# motor_board_tmc.net
KiCad netlist of a schematic drawn in EAGLE
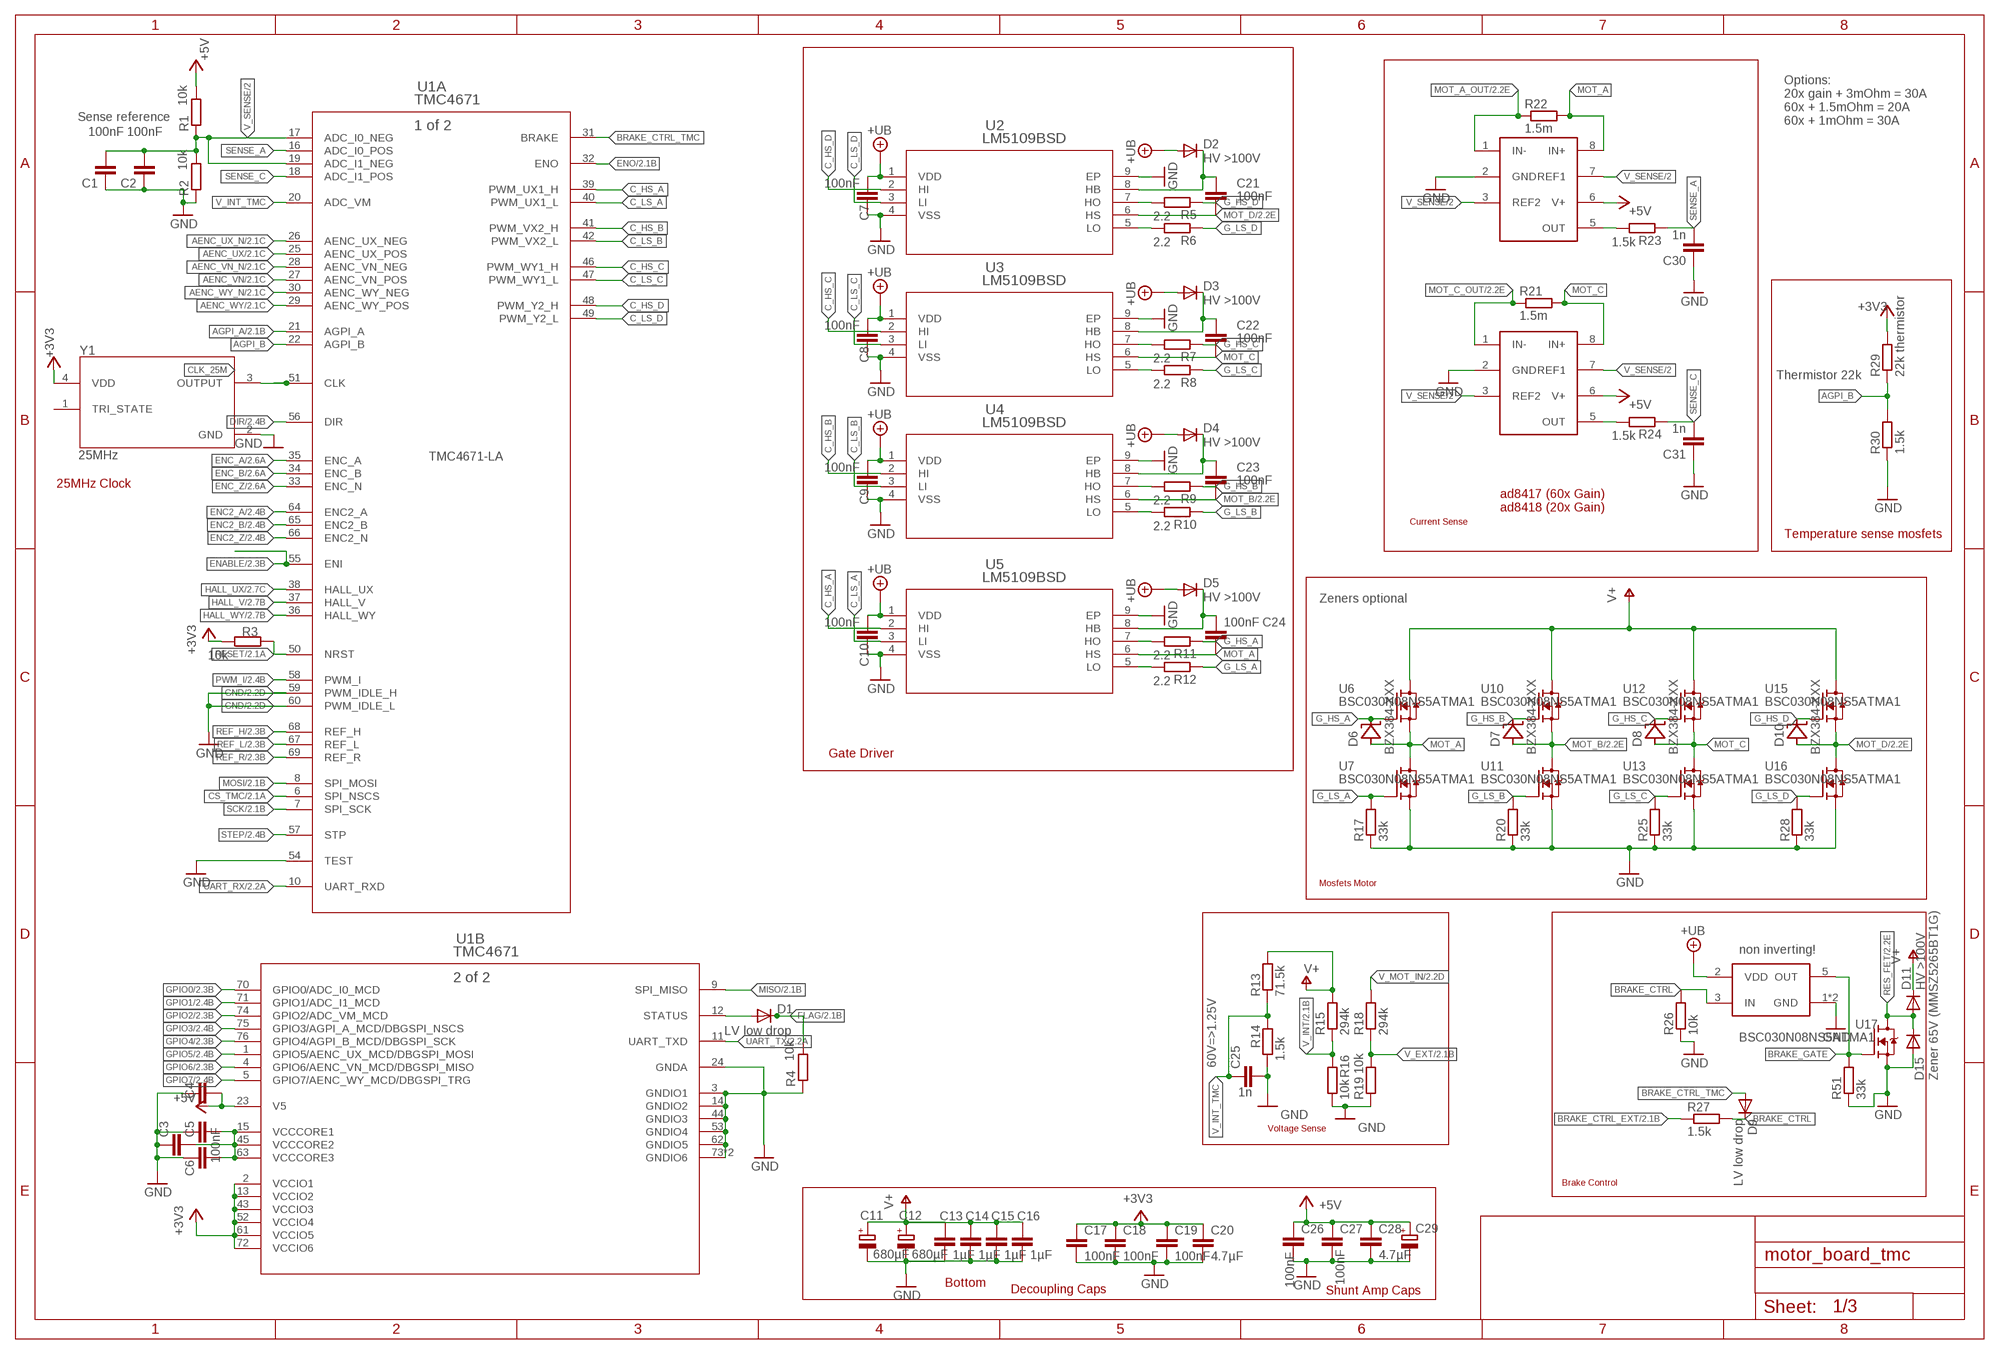
[diagram p0: schematic, sheet 1]
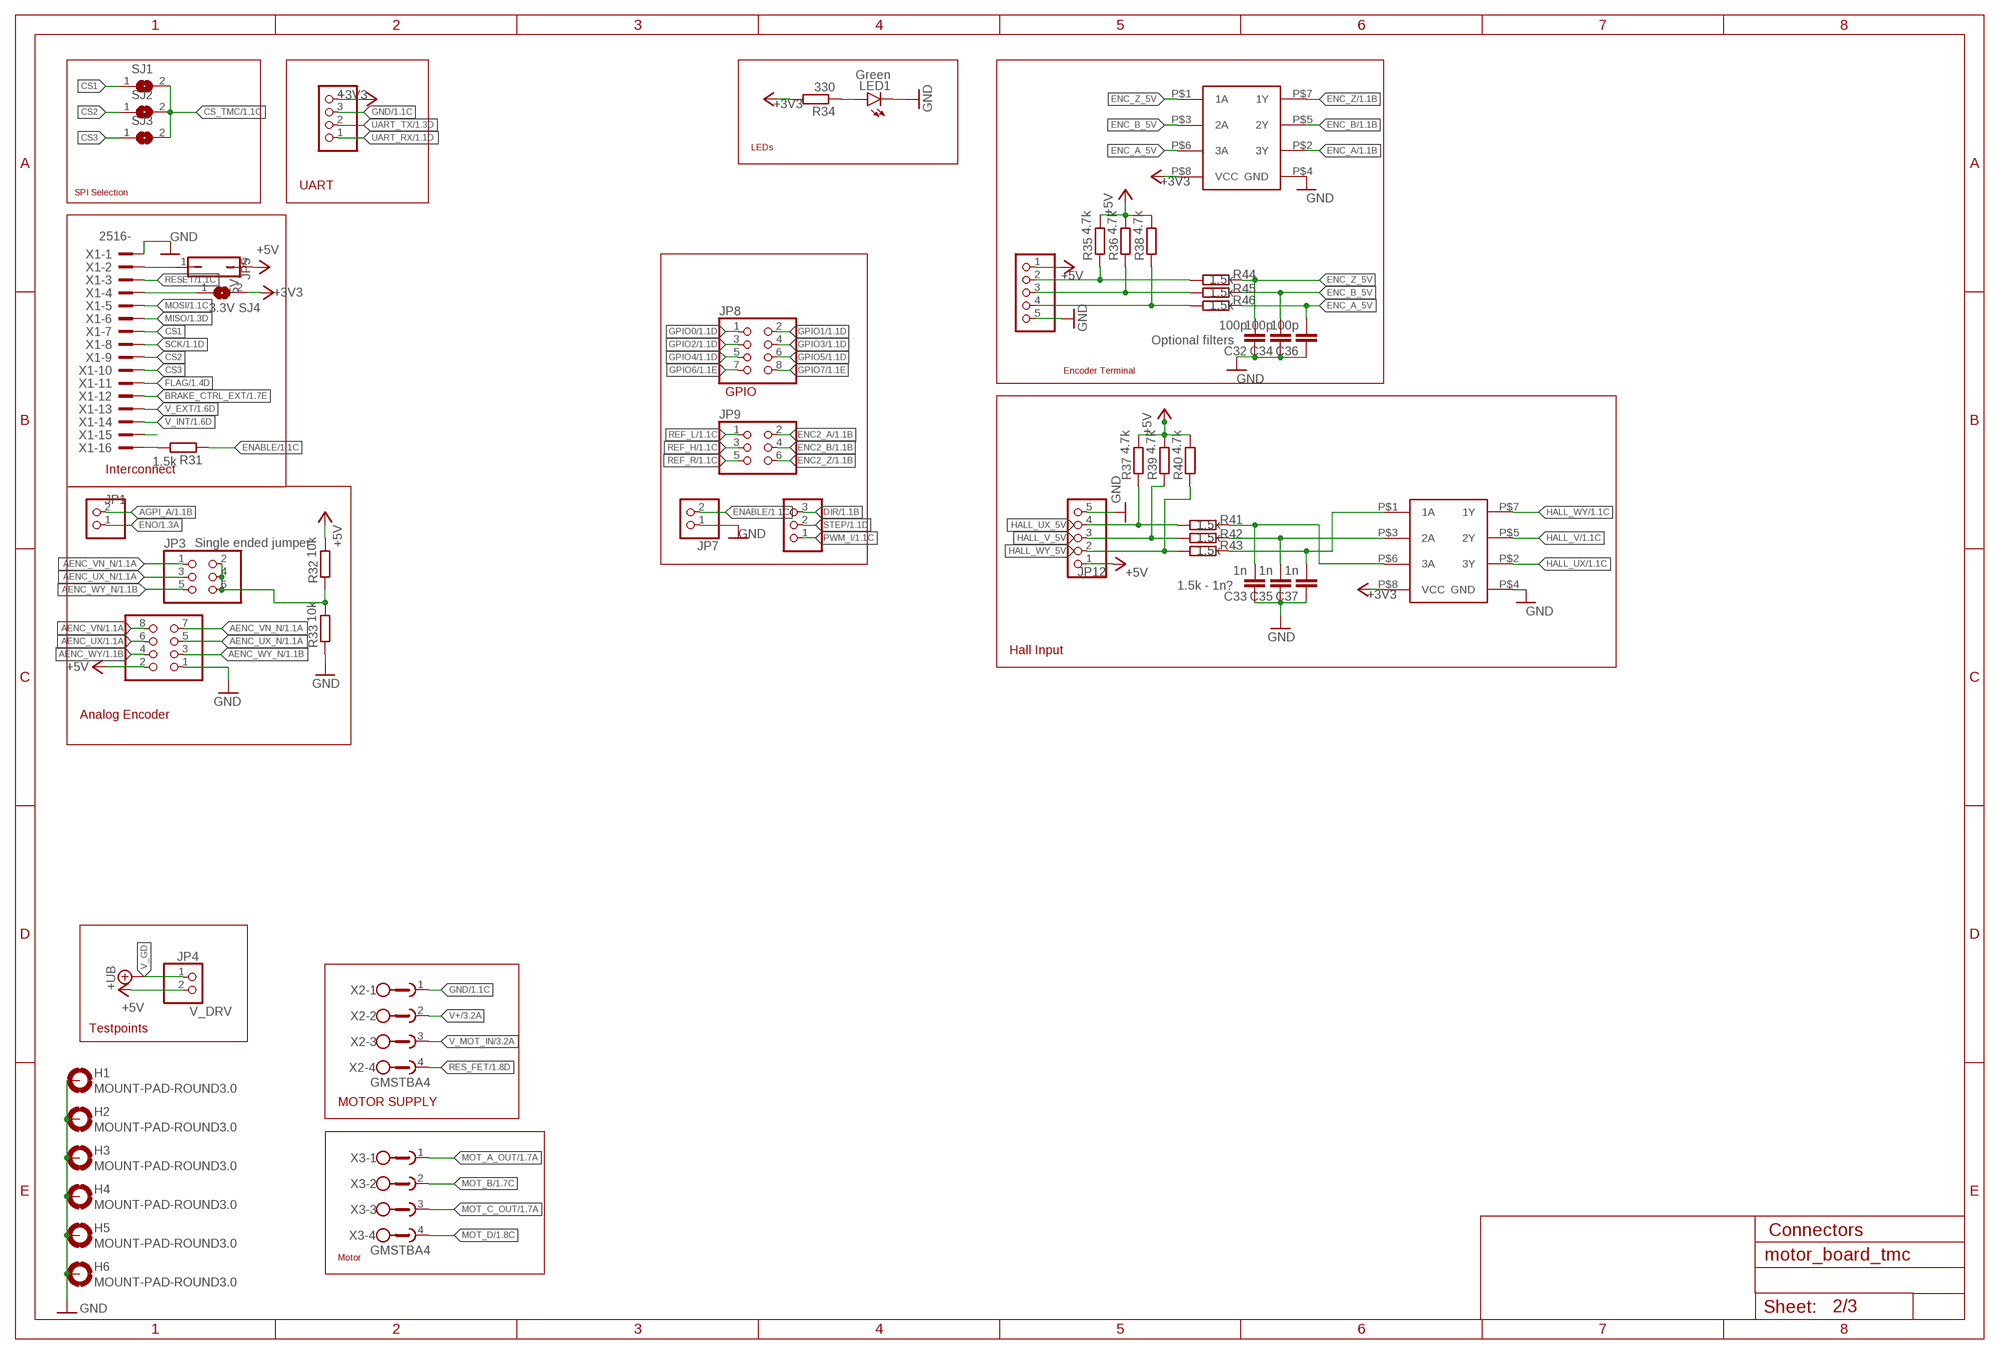
[diagram p1: schematic, sheet 2]
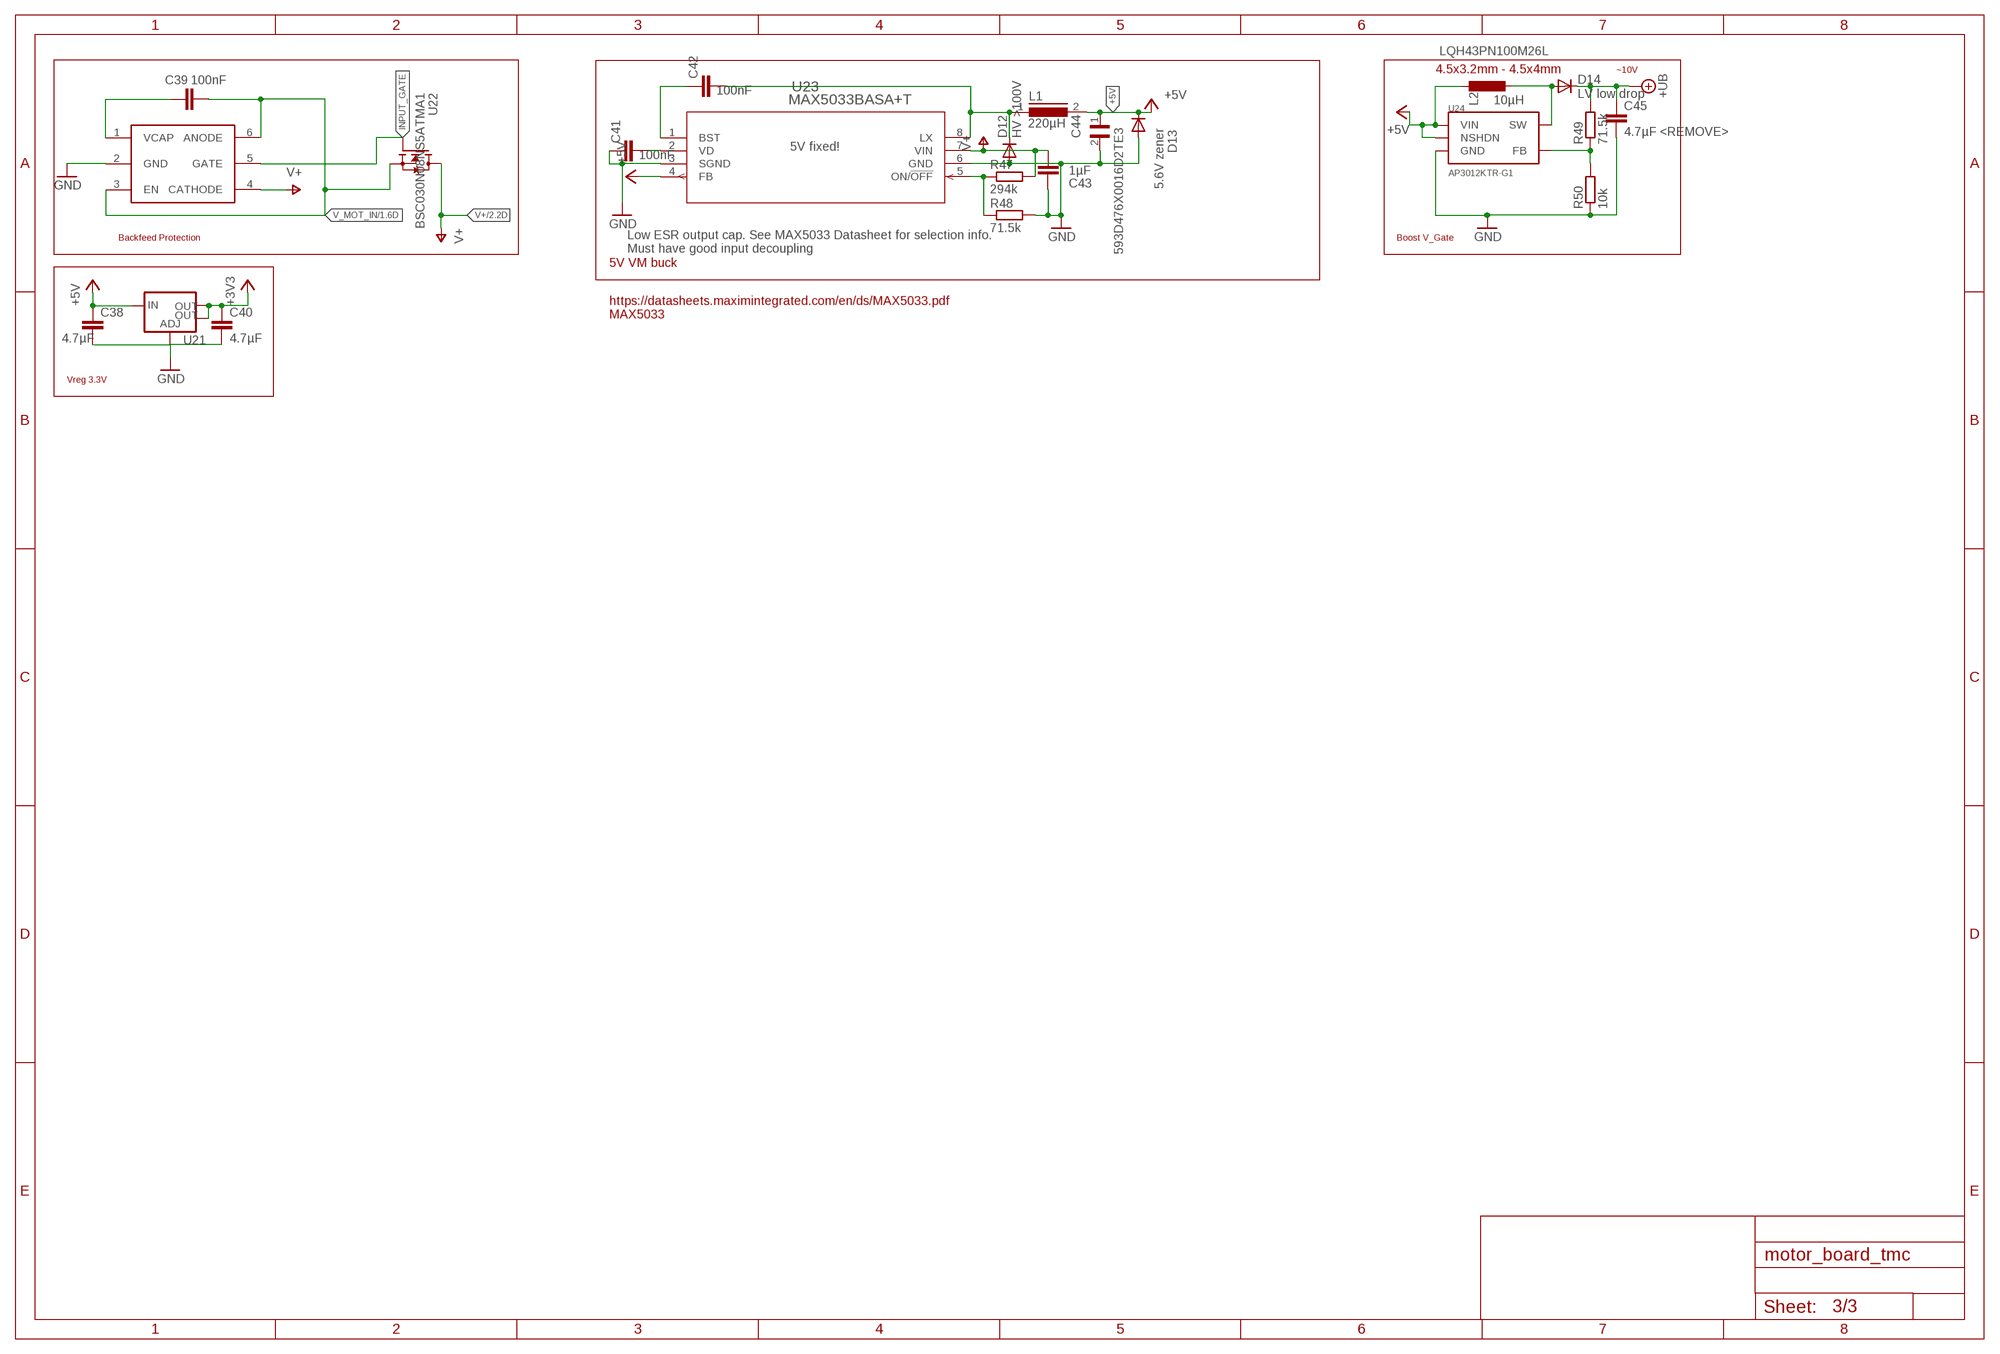
[diagram p2: schematic, sheet 3]

(export (version "E")
  (design (tool "Eeschema 10.0.6"))
  (components
    (comp (ref "C32")
      (value "100p")
      (footprint "eagle-import:C0603")
      (libsource (lib "eagle-import") (part "C-EUC0603"))
    )
    (comp (ref "C33")
      (value "1n")
      (footprint "eagle-import:C0603")
      (libsource (lib "eagle-import") (part "C-EUC0603"))
    )
    (comp (ref "C34")
      (value "100p")
      (footprint "eagle-import:C0603")
      (libsource (lib "eagle-import") (part "C-EUC0603"))
    )
    (comp (ref "C35")
      (value "1n")
      (footprint "eagle-import:C0603")
      (libsource (lib "eagle-import") (part "C-EUC0603"))
    )
    (comp (ref "C36")
      (value "100p")
      (footprint "eagle-import:C0603")
      (libsource (lib "eagle-import") (part "C-EUC0603"))
    )
    (comp (ref "C37")
      (value "1n")
      (footprint "eagle-import:C0603")
      (libsource (lib "eagle-import") (part "C-EUC0603"))
    )
    (comp (ref "H1")
      (value "MOUNT-PAD-ROUND3.0")
      (footprint "eagle-import:3,0-PAD")
      (libsource (lib "eagle-import") (part "MOUNT-PAD-ROUND3.0"))
    )
    (comp (ref "H2")
      (value "MOUNT-PAD-ROUND3.0")
      (footprint "eagle-import:3,0-PAD")
      (libsource (lib "eagle-import") (part "MOUNT-PAD-ROUND3.0"))
    )
    (comp (ref "H3")
      (value "MOUNT-PAD-ROUND3.0")
      (footprint "eagle-import:3,0-PAD")
      (libsource (lib "eagle-import") (part "MOUNT-PAD-ROUND3.0"))
    )
    (comp (ref "H4")
      (value "MOUNT-PAD-ROUND3.0")
      (footprint "eagle-import:3,0-PAD")
      (libsource (lib "eagle-import") (part "MOUNT-PAD-ROUND3.0"))
    )
    (comp (ref "H5")
      (value "MOUNT-PAD-ROUND3.0")
      (footprint "eagle-import:3,0-PAD")
      (libsource (lib "eagle-import") (part "MOUNT-PAD-ROUND3.0"))
    )
    (comp (ref "H6")
      (value "MOUNT-PAD-ROUND3.0")
      (footprint "eagle-import:3,0-PAD")
      (libsource (lib "eagle-import") (part "MOUNT-PAD-ROUND3.0"))
    )
    (comp (ref "JP1")
      (value "PINHD-1X2")
      (footprint "eagle-import:1X02")
      (libsource (lib "eagle-import") (part "PINHD-1X2"))
    )
    (comp (ref "JP2")
      (value "PINHD-2X4")
      (footprint "eagle-import:2X04")
      (libsource (lib "eagle-import") (part "PINHD-2X4"))
    )
    (comp (ref "JP3")
      (value "PINHD-2X3")
      (footprint "eagle-import:2X03")
      (libsource (lib "eagle-import") (part "PINHD-2X3"))
    )
    (comp (ref "JP4")
      (value "V_DRV")
      (footprint "eagle-import:1X02")
      (libsource (lib "eagle-import") (part "PINHD-1X2"))
    )
    (comp (ref "JP5")
      (value "5V")
      (footprint "eagle-import:JP1")
      (libsource (lib "eagle-import") (part "JP1Q"))
    )
    (comp (ref "JP6")
      (value "PINHD-1X4")
      (footprint "eagle-import:1X04")
      (libsource (lib "eagle-import") (part "PINHD-1X4"))
    )
    (comp (ref "JP7")
      (value "PINHD-1X2")
      (footprint "eagle-import:1X02")
      (libsource (lib "eagle-import") (part "PINHD-1X2"))
    )
    (comp (ref "JP8")
      (value "PINHD-2X4")
      (footprint "eagle-import:2X04")
      (libsource (lib "eagle-import") (part "PINHD-2X4"))
    )
    (comp (ref "JP9")
      (value "PINHD-2X3")
      (footprint "eagle-import:2X03")
      (libsource (lib "eagle-import") (part "PINHD-2X3"))
    )
    (comp (ref "JP10")
      (value "PINHD-1X3")
      (footprint "eagle-import:1X03")
      (libsource (lib "eagle-import") (part "PINHD-1X3"))
    )
    (comp (ref "JP11")
      (value "PINHD-1X5")
      (footprint "eagle-import:1X05")
      (libsource (lib "eagle-import") (part "PINHD-1X5"))
    )
    (comp (ref "JP12")
      (value "PINHD-1X5")
      (footprint "eagle-import:1X05")
      (libsource (lib "eagle-import") (part "PINHD-1X5"))
    )
    (comp (ref "LED1")
      (value "Green")
      (footprint "eagle-import:SML0805")
      (libsource (lib "eagle-import") (part "LEDSML0805"))
    )
    (comp (ref "R31")
      (value "1.5k")
      (footprint "eagle-import:R0603")
      (libsource (lib "eagle-import") (part "R-EU_R0603"))
    )
    (comp (ref "R32")
      (value "10k")
      (footprint "eagle-import:R0603")
      (libsource (lib "eagle-import") (part "R-EU_R0603"))
    )
    (comp (ref "R33")
      (value "10k")
      (footprint "eagle-import:R0603")
      (libsource (lib "eagle-import") (part "R-EU_R0603"))
    )
    (comp (ref "R34")
      (value "330")
      (footprint "eagle-import:R0603")
      (libsource (lib "eagle-import") (part "R-EU_R0603"))
    )
    (comp (ref "R35")
      (value "4.7k")
      (footprint "eagle-import:R0603")
      (libsource (lib "eagle-import") (part "R-EU_R0603"))
    )
    (comp (ref "R36")
      (value "4.7k")
      (footprint "eagle-import:R0603")
      (libsource (lib "eagle-import") (part "R-EU_R0603"))
    )
    (comp (ref "R37")
      (value "4.7k")
      (footprint "eagle-import:R0603")
      (libsource (lib "eagle-import") (part "R-EU_R0603"))
    )
    (comp (ref "R38")
      (value "4.7k")
      (footprint "eagle-import:R0603")
      (libsource (lib "eagle-import") (part "R-EU_R0603"))
    )
    (comp (ref "R39")
      (value "4.7k")
      (footprint "eagle-import:R0603")
      (libsource (lib "eagle-import") (part "R-EU_R0603"))
    )
    (comp (ref "R40")
      (value "4.7k")
      (footprint "eagle-import:R0603")
      (libsource (lib "eagle-import") (part "R-EU_R0603"))
    )
    (comp (ref "R41")
      (value "1.5k")
      (footprint "eagle-import:R0603")
      (libsource (lib "eagle-import") (part "R-EU_R0603"))
    )
    (comp (ref "R42")
      (value "1.5k")
      (footprint "eagle-import:R0603")
      (libsource (lib "eagle-import") (part "R-EU_R0603"))
    )
    (comp (ref "R43")
      (value "1.5k")
      (footprint "eagle-import:R0603")
      (libsource (lib "eagle-import") (part "R-EU_R0603"))
    )
    (comp (ref "R44")
      (value "1.5k")
      (footprint "eagle-import:R0603")
      (libsource (lib "eagle-import") (part "R-EU_R0603"))
    )
    (comp (ref "R45")
      (value "1.5k")
      (footprint "eagle-import:R0603")
      (libsource (lib "eagle-import") (part "R-EU_R0603"))
    )
    (comp (ref "R46")
      (value "1.5k")
      (footprint "eagle-import:R0603")
      (libsource (lib "eagle-import") (part "R-EU_R0603"))
    )
    (comp (ref "SJ1") (value "SJ") (footprint "eagle-import:SJ") (libsource (lib "eagle-import") (part "SJ")))
    (comp (ref "SJ2") (value "SJ") (footprint "eagle-import:SJ") (libsource (lib "eagle-import") (part "SJ")))
    (comp (ref "SJ3") (value "SJ") (footprint "eagle-import:SJ") (libsource (lib "eagle-import") (part "SJ")))
    (comp (ref "SJ4")
      (value "3.3V")
      (footprint "eagle-import:SJ")
      (libsource (lib "eagle-import") (part "SJ"))
    )
    (comp (ref "U18")
      (value "NC7NZ17K8X-3-BUFFER")
      (footprint "eagle-import:VFSOP-8")
      (libsource (lib "eagle-import") (part "NC7NZ17K8X-3-BUFFER"))
    )
    (comp (ref "U19")
      (value "NC7NZ17K8X-3-BUFFER")
      (footprint "eagle-import:VFSOP-8")
      (libsource (lib "eagle-import") (part "NC7NZ17K8X-3-BUFFER"))
    )
    (comp (ref "X1")
      (value "2516-")
      (footprint "eagle-import:PAK100_2500-16")
      (libsource (lib "eagle-import") (part "2516-"))
    )
    (comp (ref "X2")
      (value "GMSTBA4")
      (footprint "eagle-import:GMSTBA4")
      (fields (field (name "MF") "FARNELL") (field (name "MPN") "1757268"))
      (libsource (lib "eagle-import") (part "GMSTBA4"))
    )
    (comp (ref "X3")
      (value "GMSTBA4")
      (footprint "eagle-import:GMSTBA4")
      (fields (field (name "MF") "FARNELL") (field (name "MPN") "1757268"))
      (libsource (lib "eagle-import") (part "GMSTBA4"))
    )
    (comp (ref "C38")
      (value "4.7µF")
      (footprint "eagle-import:C0805")
      (libsource (lib "eagle-import") (part "C-EUC0805"))
    )
    (comp (ref "C39")
      (value "100nF")
      (footprint "eagle-import:C0805")
      (libsource (lib "eagle-import") (part "C-EUC0805"))
    )
    (comp (ref "C40")
      (value "4.7µF")
      (footprint "eagle-import:C0805")
      (libsource (lib "eagle-import") (part "C-EUC0805"))
    )
    (comp (ref "C41")
      (value "100nF")
      (footprint "eagle-import:C0603")
      (libsource (lib "eagle-import") (part "C-EUC0603"))
    )
    (comp (ref "C42")
      (value "100nF")
      (footprint "eagle-import:C0603")
      (libsource (lib "eagle-import") (part "C-EUC0603"))
    )
    (comp (ref "C43")
      (value "1µF")
      (footprint "eagle-import:C1206")
      (libsource (lib "eagle-import") (part "C-EUC1206"))
    )
    (comp (ref "C44")
      (value "593D476X0016D2TE3")
      (footprint "eagle-import:CAPPM7343X310N")
      (fields (field (name "DIGI-KEY_PART_NUMBER") "718-2142-1-ND") (field (name "MF") "Vishay Sprague"))
      (libsource (lib "eagle-import") (part "593D476X0016D2TE3"))
    )
    (comp (ref "C45")
      (value "4.7µF <REMOVE>")
      (footprint "eagle-import:C0805")
      (libsource (lib "eagle-import") (part "C-EUC0805"))
    )
    (comp (ref "D12")
      (value "HV >100V")
      (footprint "eagle-import:SOD-123FL")
      (libsource (lib "eagle-import") (part "DIODE_SOD-123FL"))
    )
    (comp (ref "D13")
      (value "5.6V zener")
      (footprint "eagle-import:SOD-123FL")
      (libsource (lib "eagle-import") (part "DIODE_SOD-123FL"))
    )
    (comp (ref "D14")
      (value "LV low drop")
      (footprint "eagle-import:SOD-123FL")
      (libsource (lib "eagle-import") (part "DIODE_SOD-123FL"))
    )
    (comp (ref "L1")
      (value "220µH")
      (footprint "eagle-import:8MMINDUCTOR")
      (libsource (lib "eagle-import") (part "8MMINDUCTOR"))
    )
    (comp (ref "L2")
      (value "10µH")
      (footprint "eagle-import:L4532P")
      (libsource (lib "eagle-import") (part "L-EUL4532P"))
    )
    (comp (ref "R47")
      (value "294k")
      (footprint "eagle-import:R0805")
      (libsource (lib "eagle-import") (part "R-EU_R0805"))
    )
    (comp (ref "R48")
      (value "71.5k")
      (footprint "eagle-import:R0805")
      (libsource (lib "eagle-import") (part "R-EU_R0805"))
    )
    (comp (ref "R49")
      (value "71.5k")
      (footprint "eagle-import:R0805")
      (libsource (lib "eagle-import") (part "R-EU_R0805"))
    )
    (comp (ref "R50")
      (value "10k")
      (footprint "eagle-import:R0603")
      (libsource (lib "eagle-import") (part "R-EU_R0603"))
    )
    (comp (ref "U20")
      (value "LM74700-Q1")
      (footprint "eagle-import:SOT23-6")
      (libsource (lib "eagle-import") (part "LM74700-Q1"))
    )
    (comp (ref "U21")
      (value "V_REG_LM1117SOT223")
      (footprint "eagle-import:SOT223")
      (libsource (lib "eagle-import") (part "V_REG_LM1117SOT223"))
    )
    (comp (ref "U22")
      (value "BSC030N08NS5ATMA1")
      (footprint "eagle-import:MOSFET_BSC093N04LSGATMA1")
      (fields (field (name "MF") "Infineon Technologies"))
      (libsource (lib "eagle-import") (part "BSC030N08NS5ATMA1"))
    )
    (comp (ref "U23")
      (value "MAX5033BASA+T")
      (footprint "eagle-import:21-0041B_8_MXM")
      (fields (field (name "MANUFACTURER_PART_NUMBER") "max5033basa+T"))
      (libsource (lib "eagle-import") (part "MAX5033BASA+T"))
    )
    (comp (ref "U24")
      (value "AP3012KTR-G1")
      (footprint "eagle-import:SOT23-5L")
      (libsource (lib "eagle-import") (part "AP3012KTR-G1"))
    )
    (comp (ref "C1")
      (value "100nF")
      (footprint "eagle-import:C0603")
      (libsource (lib "eagle-import") (part "C-EUC0603"))
    )
    (comp (ref "C2")
      (value "100nF")
      (footprint "eagle-import:C0603")
      (libsource (lib "eagle-import") (part "C-EUC0603"))
    )
    (comp (ref "C3")
      (value "100nF")
      (footprint "eagle-import:C0603")
      (libsource (lib "eagle-import") (part "C-EUC0603"))
    )
    (comp (ref "C4")
      (value "100nF")
      (footprint "eagle-import:C0603")
      (libsource (lib "eagle-import") (part "C-EUC0603"))
    )
    (comp (ref "C5")
      (value "100nF")
      (footprint "eagle-import:C0603")
      (libsource (lib "eagle-import") (part "C-EUC0603"))
    )
    (comp (ref "C6")
      (value "100nF")
      (footprint "eagle-import:C0603")
      (libsource (lib "eagle-import") (part "C-EUC0603"))
    )
    (comp (ref "C7")
      (value "100nF")
      (footprint "eagle-import:C0603")
      (libsource (lib "eagle-import") (part "C-EUC0603"))
    )
    (comp (ref "C8")
      (value "100nF")
      (footprint "eagle-import:C0603")
      (libsource (lib "eagle-import") (part "C-EUC0603"))
    )
    (comp (ref "C9")
      (value "100nF")
      (footprint "eagle-import:C0603")
      (libsource (lib "eagle-import") (part "C-EUC0603"))
    )
    (comp (ref "C10")
      (value "100nF")
      (footprint "eagle-import:C0603")
      (libsource (lib "eagle-import") (part "C-EUC0603"))
    )
    (comp (ref "C11")
      (value "680µF")
      (footprint "eagle-import:E7,5-16")
      (libsource (lib "eagle-import") (part "CPOL-EUE7.5-16"))
    )
    (comp (ref "C12")
      (value "680µF")
      (footprint "eagle-import:E7,5-16")
      (libsource (lib "eagle-import") (part "CPOL-EUE7.5-16"))
    )
    (comp (ref "C13")
      (value "1µF")
      (footprint "eagle-import:C1206")
      (libsource (lib "eagle-import") (part "C-EUC1206"))
    )
    (comp (ref "C14")
      (value "1µF")
      (footprint "eagle-import:C1206")
      (libsource (lib "eagle-import") (part "C-EUC1206"))
    )
    (comp (ref "C15")
      (value "1µF")
      (footprint "eagle-import:C1206")
      (libsource (lib "eagle-import") (part "C-EUC1206"))
    )
    (comp (ref "C16")
      (value "1µF")
      (footprint "eagle-import:C1206")
      (libsource (lib "eagle-import") (part "C-EUC1206"))
    )
    (comp (ref "C17")
      (value "100nF")
      (footprint "eagle-import:C0603")
      (libsource (lib "eagle-import") (part "C-EUC0603"))
    )
    (comp (ref "C18")
      (value "100nF")
      (footprint "eagle-import:C0603")
      (libsource (lib "eagle-import") (part "C-EUC0603"))
    )
    (comp (ref "C19")
      (value "100nF")
      (footprint "eagle-import:C0603")
      (libsource (lib "eagle-import") (part "C-EUC0603"))
    )
    (comp (ref "C20")
      (value "4.7µF")
      (footprint "eagle-import:C0805")
      (libsource (lib "eagle-import") (part "C-EUC0805"))
    )
    (comp (ref "C21")
      (value "100nF")
      (footprint "eagle-import:C0805")
      (libsource (lib "eagle-import") (part "C-EUC0805"))
    )
    (comp (ref "C22")
      (value "100nF")
      (footprint "eagle-import:C0805")
      (libsource (lib "eagle-import") (part "C-EUC0805"))
    )
    (comp (ref "C23")
      (value "100nF")
      (footprint "eagle-import:C0805")
      (libsource (lib "eagle-import") (part "C-EUC0805"))
    )
    (comp (ref "C24")
      (value "100nF")
      (footprint "eagle-import:C0805")
      (libsource (lib "eagle-import") (part "C-EUC0805"))
    )
    (comp (ref "C25")
      (value "1n")
      (footprint "eagle-import:C0603")
      (libsource (lib "eagle-import") (part "C-EUC0603"))
    )
    (comp (ref "C26")
      (value "100nF")
      (footprint "eagle-import:C0603")
      (libsource (lib "eagle-import") (part "C-EUC0603"))
    )
    (comp (ref "C27")
      (value "100nF")
      (footprint "eagle-import:C0603")
      (libsource (lib "eagle-import") (part "C-EUC0603"))
    )
    (comp (ref "C28")
      (value "4.7µF")
      (footprint "eagle-import:C0805")
      (libsource (lib "eagle-import") (part "C-EUC0805"))
    )
    (comp (ref "C29")
      (value "CPOL-EUE5-8.5")
      (footprint "eagle-import:E5-8,5")
      (libsource (lib "eagle-import") (part "CPOL-EUE5-8.5"))
    )
    (comp (ref "C30")
      (value "1n")
      (footprint "eagle-import:C0603")
      (libsource (lib "eagle-import") (part "C-EUC0603"))
    )
    (comp (ref "C31")
      (value "1n")
      (footprint "eagle-import:C0603")
      (libsource (lib "eagle-import") (part "C-EUC0603"))
    )
    (comp (ref "D1")
      (value "LV low drop")
      (footprint "eagle-import:SOD-123FL")
      (libsource (lib "eagle-import") (part "DIODE_SOD-123FL"))
    )
    (comp (ref "D2")
      (value "HV >100V")
      (footprint "eagle-import:SOD-123FL")
      (libsource (lib "eagle-import") (part "DIODE_SOD-123FL"))
    )
    (comp (ref "D3")
      (value "HV >100V")
      (footprint "eagle-import:SOD-123FL")
      (libsource (lib "eagle-import") (part "DIODE_SOD-123FL"))
    )
    (comp (ref "D4")
      (value "HV >100V")
      (footprint "eagle-import:SOD-123FL")
      (libsource (lib "eagle-import") (part "DIODE_SOD-123FL"))
    )
    (comp (ref "D5")
      (value "HV >100V")
      (footprint "eagle-import:SOD-123FL")
      (libsource (lib "eagle-import") (part "DIODE_SOD-123FL"))
    )
    (comp (ref "D6")
      (value "BZX384-XXX")
      (footprint "eagle-import:SOD323-R")
      (libsource (lib "eagle-import") (part "BZX384-XXX"))
    )
    (comp (ref "D7")
      (value "BZX384-XXX")
      (footprint "eagle-import:SOD323-R")
      (libsource (lib "eagle-import") (part "BZX384-XXX"))
    )
    (comp (ref "D8")
      (value "BZX384-XXX")
      (footprint "eagle-import:SOD323-R")
      (libsource (lib "eagle-import") (part "BZX384-XXX"))
    )
    (comp (ref "D9")
      (value "LV low drop")
      (footprint "eagle-import:SOD-123FL")
      (libsource (lib "eagle-import") (part "DIODE_SOD-123FL"))
    )
    (comp (ref "D10")
      (value "BZX384-XXX")
      (footprint "eagle-import:SOD323-R")
      (libsource (lib "eagle-import") (part "BZX384-XXX"))
    )
    (comp (ref "D11")
      (value "HV >100V")
      (footprint "eagle-import:SOD-123FL")
      (libsource (lib "eagle-import") (part "DIODE_SOD-123FL"))
    )
    (comp (ref "D15")
      (value "Zener 65V (MMSZ5265BT1G)")
      (footprint "eagle-import:SOD-123FL")
      (libsource (lib "eagle-import") (part "DIODE_SOD-123FL"))
    )
    (comp (ref "R1")
      (value "10k")
      (footprint "eagle-import:R0603")
      (libsource (lib "eagle-import") (part "R-EU_R0603"))
    )
    (comp (ref "R2")
      (value "10k")
      (footprint "eagle-import:R0603")
      (libsource (lib "eagle-import") (part "R-EU_R0603"))
    )
    (comp (ref "R3")
      (value "10k")
      (footprint "eagle-import:R0603")
      (libsource (lib "eagle-import") (part "R-EU_R0603"))
    )
    (comp (ref "R4")
      (value "10k")
      (footprint "eagle-import:R0603")
      (libsource (lib "eagle-import") (part "R-EU_R0603"))
    )
    (comp (ref "R5")
      (value "2.2")
      (footprint "eagle-import:R0603")
      (libsource (lib "eagle-import") (part "R-EU_R0603"))
    )
    (comp (ref "R6")
      (value "2.2")
      (footprint "eagle-import:R0603")
      (libsource (lib "eagle-import") (part "R-EU_R0603"))
    )
    (comp (ref "R7")
      (value "2.2")
      (footprint "eagle-import:R0603")
      (libsource (lib "eagle-import") (part "R-EU_R0603"))
    )
    (comp (ref "R8")
      (value "2.2")
      (footprint "eagle-import:R0603")
      (libsource (lib "eagle-import") (part "R-EU_R0603"))
    )
    (comp (ref "R9")
      (value "2.2")
      (footprint "eagle-import:R0603")
      (libsource (lib "eagle-import") (part "R-EU_R0603"))
    )
    (comp (ref "R10")
      (value "2.2")
      (footprint "eagle-import:R0603")
      (libsource (lib "eagle-import") (part "R-EU_R0603"))
    )
    (comp (ref "R11")
      (value "2.2")
      (footprint "eagle-import:R0603")
      (libsource (lib "eagle-import") (part "R-EU_R0603"))
    )
    (comp (ref "R12")
      (value "2.2")
      (footprint "eagle-import:R0603")
      (libsource (lib "eagle-import") (part "R-EU_R0603"))
    )
    (comp (ref "R13")
      (value "71.5k")
      (footprint "eagle-import:R0805")
      (libsource (lib "eagle-import") (part "R-EU_R0805"))
    )
    (comp (ref "R14")
      (value "1.5k")
      (footprint "eagle-import:R0603")
      (libsource (lib "eagle-import") (part "R-EU_R0603"))
    )
    (comp (ref "R15")
      (value "294k")
      (footprint "eagle-import:R0805")
      (libsource (lib "eagle-import") (part "R-EU_R0805"))
    )
    (comp (ref "R16")
      (value "10k")
      (footprint "eagle-import:R0603")
      (libsource (lib "eagle-import") (part "R-EU_R0603"))
    )
    (comp (ref "R17")
      (value "33k")
      (footprint "eagle-import:R0603")
      (libsource (lib "eagle-import") (part "R-EU_R0603"))
    )
    (comp (ref "R18")
      (value "294k")
      (footprint "eagle-import:R0805")
      (libsource (lib "eagle-import") (part "R-EU_R0805"))
    )
    (comp (ref "R19")
      (value "10k")
      (footprint "eagle-import:R0603")
      (libsource (lib "eagle-import") (part "R-EU_R0603"))
    )
    (comp (ref "R20")
      (value "33k")
      (footprint "eagle-import:R0603")
      (libsource (lib "eagle-import") (part "R-EU_R0603"))
    )
    (comp (ref "R21")
      (value "1.5m")
      (footprint "eagle-import:R2512")
      (libsource (lib "eagle-import") (part "R-EU_R2512"))
    )
    (comp (ref "R22")
      (value "1.5m")
      (footprint "eagle-import:R2512")
      (libsource (lib "eagle-import") (part "R-EU_R2512"))
    )
    (comp (ref "R23")
      (value "1.5k")
      (footprint "eagle-import:R0603")
      (libsource (lib "eagle-import") (part "R-EU_R0603"))
    )
    (comp (ref "R24")
      (value "1.5k")
      (footprint "eagle-import:R0603")
      (libsource (lib "eagle-import") (part "R-EU_R0603"))
    )
    (comp (ref "R25")
      (value "33k")
      (footprint "eagle-import:R0603")
      (libsource (lib "eagle-import") (part "R-EU_R0603"))
    )
    (comp (ref "R26")
      (value "10k")
      (footprint "eagle-import:R0603")
      (libsource (lib "eagle-import") (part "R-EU_R0603"))
    )
    (comp (ref "R27")
      (value "1.5k")
      (footprint "eagle-import:R0603")
      (libsource (lib "eagle-import") (part "R-EU_R0603"))
    )
    (comp (ref "R28")
      (value "33k")
      (footprint "eagle-import:R0603")
      (libsource (lib "eagle-import") (part "R-EU_R0603"))
    )
    (comp (ref "R29")
      (value "22k thermistor")
      (footprint "eagle-import:R0603")
      (libsource (lib "eagle-import") (part "R-EU_R0603"))
    )
    (comp (ref "R30")
      (value "1.5k")
      (footprint "eagle-import:R0603")
      (libsource (lib "eagle-import") (part "R-EU_R0603"))
    )
    (comp (ref "R51")
      (value "33k")
      (footprint "eagle-import:R0603")
      (libsource (lib "eagle-import") (part "R-EU_R0603"))
    )
    (comp (ref "U1")
      (value "TMC4671")
      (footprint "eagle-import:QFN76_10P5X6P5")
      (fields (field (name "MANUFACTURER_PART_NUMBER") "TMC4671ES"))
      (libsource (lib "eagle-import") (part "TMC4671"))
    )
    (comp (ref "U2")
      (value "LM5109BSD")
      (footprint "eagle-import:SDC08A")
      (fields (field (name "MANUFACTURER_PART_NUMBER") "lm5109bsd"))
      (libsource (lib "eagle-import") (part "LM5109BSD"))
    )
    (comp (ref "U3")
      (value "LM5109BSD")
      (footprint "eagle-import:SDC08A")
      (fields (field (name "MANUFACTURER_PART_NUMBER") "lm5109bsd"))
      (libsource (lib "eagle-import") (part "LM5109BSD"))
    )
    (comp (ref "U4")
      (value "LM5109BSD")
      (footprint "eagle-import:SDC08A")
      (fields (field (name "MANUFACTURER_PART_NUMBER") "lm5109bsd"))
      (libsource (lib "eagle-import") (part "LM5109BSD"))
    )
    (comp (ref "U5")
      (value "LM5109BSD")
      (footprint "eagle-import:SDC08A")
      (fields (field (name "MANUFACTURER_PART_NUMBER") "lm5109bsd"))
      (libsource (lib "eagle-import") (part "LM5109BSD"))
    )
    (comp (ref "U6")
      (value "BSC030N08NS5ATMA1")
      (footprint "eagle-import:MOSFET_BSC093N04LSGATMA1")
      (fields (field (name "MF") "Infineon Technologies"))
      (libsource (lib "eagle-import") (part "BSC030N08NS5ATMA1"))
    )
    (comp (ref "U7")
      (value "BSC030N08NS5ATMA1")
      (footprint "eagle-import:MOSFET_BSC093N04LSGATMA1")
      (fields (field (name "MF") "Infineon Technologies"))
      (libsource (lib "eagle-import") (part "BSC030N08NS5ATMA1"))
    )
    (comp (ref "U8")
      (value "AD841X")
      (footprint "eagle-import:MSOP8")
      (libsource (lib "eagle-import") (part "AD841X"))
    )
    (comp (ref "U9")
      (value "AD841X")
      (footprint "eagle-import:MSOP8")
      (libsource (lib "eagle-import") (part "AD841X"))
    )
    (comp (ref "U10")
      (value "BSC030N08NS5ATMA1")
      (footprint "eagle-import:MOSFET_BSC093N04LSGATMA1")
      (fields (field (name "MF") "Infineon Technologies"))
      (libsource (lib "eagle-import") (part "BSC030N08NS5ATMA1"))
    )
    (comp (ref "U11")
      (value "BSC030N08NS5ATMA1")
      (footprint "eagle-import:MOSFET_BSC093N04LSGATMA1")
      (fields (field (name "MF") "Infineon Technologies"))
      (libsource (lib "eagle-import") (part "BSC030N08NS5ATMA1"))
    )
    (comp (ref "U12")
      (value "BSC030N08NS5ATMA1")
      (footprint "eagle-import:MOSFET_BSC093N04LSGATMA1")
      (fields (field (name "MF") "Infineon Technologies"))
      (libsource (lib "eagle-import") (part "BSC030N08NS5ATMA1"))
    )
    (comp (ref "U13")
      (value "BSC030N08NS5ATMA1")
      (footprint "eagle-import:MOSFET_BSC093N04LSGATMA1")
      (fields (field (name "MF") "Infineon Technologies"))
      (libsource (lib "eagle-import") (part "BSC030N08NS5ATMA1"))
    )
    (comp (ref "U14")
      (value "MCP14XX")
      (footprint "eagle-import:SOT23-5L")
      (libsource (lib "eagle-import") (part "MCP14XX"))
    )
    (comp (ref "U15")
      (value "BSC030N08NS5ATMA1")
      (footprint "eagle-import:MOSFET_BSC093N04LSGATMA1")
      (fields (field (name "MF") "Infineon Technologies"))
      (libsource (lib "eagle-import") (part "BSC030N08NS5ATMA1"))
    )
    (comp (ref "U16")
      (value "BSC030N08NS5ATMA1")
      (footprint "eagle-import:MOSFET_BSC093N04LSGATMA1")
      (fields (field (name "MF") "Infineon Technologies"))
      (libsource (lib "eagle-import") (part "BSC030N08NS5ATMA1"))
    )
    (comp (ref "U17")
      (value "BSC030N08NS5ATMA1")
      (footprint "eagle-import:MOSFET_BSC093N04LSGATMA1")
      (fields (field (name "MF") "Infineon Technologies"))
      (libsource (lib "eagle-import") (part "BSC030N08NS5ATMA1"))
    )
    (comp (ref "Y1")
      (value "25MHz")
      (footprint "eagle-import:ECS-327KE-TR")
      (fields
        (field (name "DIGIKEY_PART_NUMBER") "XC1751TR-ND")
        (field (name "MANUFACTURER") "ECS Inc.")
        (field (name "MPN") "ECS-327KE-TR")
        (field (name "CREATED_BY") "PCBLayout.com")
      )
      (libsource (lib "eagle-import") (part "ECS-327KE-TR"))
    )
  )
  (nets
    (net (code "1") (name "+3V3") (class "Default")
      (node (ref "C17") (pin "1") (pinfunction "1_1") (pintype "passive"))
      (node (ref "C18") (pin "1") (pinfunction "1_1") (pintype "passive"))
      (node (ref "C19") (pin "1") (pinfunction "1_1") (pintype "passive"))
      (node (ref "C20") (pin "1") (pinfunction "1_1") (pintype "passive"))
      (node (ref "C40") (pin "1") (pinfunction "1_1") (pintype "passive"))
      (node (ref "JP6") (pin "4") (pinfunction "4_4") (pintype "passive"))
      (node (ref "R29") (pin "2") (pinfunction "2_2") (pintype "passive"))
      (node (ref "R3") (pin "2") (pinfunction "2_2") (pintype "passive"))
      (node (ref "R34") (pin "2") (pinfunction "2_2") (pintype "passive"))
      (node (ref "SJ4") (pin "2") (pinfunction "2_2") (pintype "passive"))
      (node (ref "U1") (pin "13") (pinfunction "VCCIO2_13") (pintype "power_in"))
      (node (ref "U1") (pin "2") (pinfunction "VCCIO1_2") (pintype "power_in"))
      (node (ref "U1") (pin "43") (pinfunction "VCCIO3_43") (pintype "power_in"))
      (node (ref "U1") (pin "52") (pinfunction "VCCIO4_52") (pintype "power_in"))
      (node (ref "U1") (pin "61") (pinfunction "VCCIO5_61") (pintype "power_in"))
      (node (ref "U1") (pin "72") (pinfunction "VCCIO6_72") (pintype "power_in"))
      (node (ref "U18") (pin "P$8") (pinfunction "VCC_P$8") (pintype "bidirectional"))
      (node (ref "U19") (pin "P$8") (pinfunction "VCC_P$8") (pintype "bidirectional"))
      (node (ref "U21") (pin "2") (pinfunction "OUT_2") (pintype "output"))
      (node (ref "U21") (pin "4") (pinfunction "OUT_4") (pintype "output"))
      (node (ref "Y1") (pin "4") (pinfunction "VDD_4") (pintype "power_in"))
    )
    (net (code "2") (name "+5V") (class "Default")
      (node (ref "C26") (pin "1") (pinfunction "1_1") (pintype "passive"))
      (node (ref "C27") (pin "1") (pinfunction "1_1") (pintype "passive"))
      (node (ref "C28") (pin "1") (pinfunction "1_1") (pintype "passive"))
      (node (ref "C29") (pin "+") (pinfunction "+_+") (pintype "passive"))
      (node (ref "C38") (pin "1") (pinfunction "1_1") (pintype "passive"))
      (node (ref "C4") (pin "2") (pinfunction "2_2") (pintype "passive"))
      (node (ref "C44") (pin "1") (pinfunction "1_1") (pintype "passive"))
      (node (ref "D13") (pin "C") (pinfunction "C_C") (pintype "passive"))
      (node (ref "JP11") (pin "1") (pinfunction "1_1") (pintype "passive"))
      (node (ref "JP12") (pin "1") (pinfunction "1_1") (pintype "passive"))
      (node (ref "JP2") (pin "2") (pinfunction "2_2") (pintype "passive"))
      (node (ref "JP4") (pin "2") (pinfunction "2_2") (pintype "passive"))
      (node (ref "JP5") (pin "2") (pinfunction "2_2") (pintype "passive"))
      (node (ref "L1") (pin "2") (pinfunction "2_2") (pintype "passive"))
      (node (ref "L2") (pin "1") (pinfunction "1_1") (pintype "passive"))
      (node (ref "R1") (pin "2") (pinfunction "2_2") (pintype "passive"))
      (node (ref "R32") (pin "2") (pinfunction "2_2") (pintype "passive"))
      (node (ref "R35") (pin "2") (pinfunction "2_2") (pintype "passive"))
      (node (ref "R36") (pin "2") (pinfunction "2_2") (pintype "passive"))
      (node (ref "R37") (pin "2") (pinfunction "2_2") (pintype "passive"))
      (node (ref "R38") (pin "2") (pinfunction "2_2") (pintype "passive"))
      (node (ref "R39") (pin "2") (pinfunction "2_2") (pintype "passive"))
      (node (ref "R40") (pin "2") (pinfunction "2_2") (pintype "passive"))
      (node (ref "U1") (pin "23") (pinfunction "V5_23") (pintype "power_in"))
      (node (ref "U21") (pin "3") (pinfunction "IN_3") (pintype "input"))
      (node (ref "U23") (pin "4") (pinfunction "FB_4") (pintype "output"))
      (node (ref "U24") (pin "4") (pinfunction "NSHDN_4") (pintype "bidirectional"))
      (node (ref "U24") (pin "5") (pinfunction "VIN_5") (pintype "bidirectional"))
      (node (ref "U8") (pin "6") (pinfunction "V+_6") (pintype "bidirectional"))
      (node (ref "U9") (pin "6") (pinfunction "V+_6") (pintype "bidirectional"))
    )
    (net (code "3") (name "AENC_UX") (class "Default")
      (node (ref "JP2") (pin "6") (pinfunction "6_6") (pintype "passive"))
      (node (ref "U1") (pin "25") (pinfunction "AENC_UX_POS_25") (pintype "input"))
    )
    (net (code "4") (name "AENC_UX_N") (class "Default")
      (node (ref "JP2") (pin "5") (pinfunction "5_5") (pintype "passive"))
      (node (ref "JP3") (pin "3") (pinfunction "3_3") (pintype "passive"))
      (node (ref "U1") (pin "26") (pinfunction "AENC_UX_NEG_26") (pintype "input"))
    )
    (net (code "5") (name "AENC_VN") (class "Default")
      (node (ref "JP2") (pin "8") (pinfunction "8_8") (pintype "passive"))
      (node (ref "U1") (pin "27") (pinfunction "AENC_VN_POS_27") (pintype "input"))
    )
    (net (code "6") (name "AENC_VN_N") (class "Default")
      (node (ref "JP2") (pin "7") (pinfunction "7_7") (pintype "passive"))
      (node (ref "JP3") (pin "1") (pinfunction "1_1") (pintype "passive"))
      (node (ref "U1") (pin "28") (pinfunction "AENC_VN_NEG_28") (pintype "input"))
    )
    (net (code "7") (name "AENC_WY") (class "Default")
      (node (ref "JP2") (pin "4") (pinfunction "4_4") (pintype "passive"))
      (node (ref "U1") (pin "29") (pinfunction "AENC_WY_POS_29") (pintype "input"))
    )
    (net (code "8") (name "AENC_WY_N") (class "Default")
      (node (ref "JP2") (pin "3") (pinfunction "3_3") (pintype "passive"))
      (node (ref "JP3") (pin "5") (pinfunction "5_5") (pintype "passive"))
      (node (ref "U1") (pin "30") (pinfunction "AENC_WY_NEG_30") (pintype "input"))
    )
    (net (code "9") (name "AGPI_A") (class "Default")
      (node (ref "JP1") (pin "2") (pinfunction "2_2") (pintype "passive"))
      (node (ref "U1") (pin "21") (pinfunction "AGPI_A_21") (pintype "input"))
    )
    (net (code "10") (name "AGPI_B") (class "Default")
      (node (ref "R29") (pin "1") (pinfunction "1_1") (pintype "passive"))
      (node (ref "R30") (pin "2") (pinfunction "2_2") (pintype "passive"))
      (node (ref "U1") (pin "22") (pinfunction "AGPI_B_22") (pintype "input"))
    )
    (net (code "11") (name "BRAKE_CTRL") (class "Default")
      (node (ref "D9") (pin "C") (pinfunction "C_C") (pintype "passive"))
      (node (ref "R26") (pin "2") (pinfunction "2_2") (pintype "passive"))
      (node (ref "R27") (pin "2") (pinfunction "2_2") (pintype "passive"))
      (node (ref "U14") (pin "3") (pinfunction "IN_3") (pintype "bidirectional"))
    )
    (net (code "12") (name "BRAKE_CTRL_EXT") (class "Default")
      (node (ref "R27") (pin "1") (pinfunction "1_1") (pintype "passive"))
      (node (ref "X1") (pin "12") (pinfunction "KL_12") (pintype "passive"))
    )
    (net (code "13") (name "BRAKE_CTRL_TMC") (class "Default")
      (node (ref "D9") (pin "A") (pinfunction "A_A") (pintype "passive"))
      (node (ref "U1") (pin "31") (pinfunction "BRAKE_31") (pintype "output"))
    )
    (net (code "14") (name "BRAKE_GATE") (class "Default")
      (node (ref "R51") (pin "2") (pinfunction "2_2") (pintype "passive"))
      (node (ref "U14") (pin "5") (pinfunction "OUT_5") (pintype "bidirectional"))
      (node (ref "U17") (pin "4") (pinfunction "G_4") (pintype "passive"))
    )
    (net (code "15") (name "CLK_25M") (class "Default")
      (node (ref "U1") (pin "51") (pinfunction "CLK_51") (pintype "input"))
      (node (ref "Y1") (pin "3") (pinfunction "OUTPUT_3") (pintype "output"))
    )
    (net (code "16") (name "CS1") (class "Default")
      (node (ref "SJ1") (pin "1") (pinfunction "1_1") (pintype "passive"))
      (node (ref "X1") (pin "7") (pinfunction "KL_7") (pintype "passive"))
    )
    (net (code "17") (name "CS2") (class "Default")
      (node (ref "SJ2") (pin "1") (pinfunction "1_1") (pintype "passive"))
      (node (ref "X1") (pin "9") (pinfunction "KL_9") (pintype "passive"))
    )
    (net (code "18") (name "CS3") (class "Default")
      (node (ref "SJ3") (pin "1") (pinfunction "1_1") (pintype "passive"))
      (node (ref "X1") (pin "10") (pinfunction "KL_10") (pintype "passive"))
    )
    (net (code "19") (name "CS_TMC") (class "Default")
      (node (ref "SJ1") (pin "2") (pinfunction "2_2") (pintype "passive"))
      (node (ref "SJ2") (pin "2") (pinfunction "2_2") (pintype "passive"))
      (node (ref "SJ3") (pin "2") (pinfunction "2_2") (pintype "passive"))
      (node (ref "U1") (pin "6") (pinfunction "SPI_NSCS_6") (pintype "input"))
    )
    (net (code "20") (name "C_HS_A") (class "Default")
      (node (ref "U1") (pin "39") (pinfunction "PWM_UX1_H_39") (pintype "output"))
      (node (ref "U5") (pin "2") (pinfunction "HI_2") (pintype "input"))
    )
    (net (code "21") (name "C_HS_B") (class "Default")
      (node (ref "U1") (pin "41") (pinfunction "PWM_VX2_H_41") (pintype "output"))
      (node (ref "U4") (pin "2") (pinfunction "HI_2") (pintype "input"))
    )
    (net (code "22") (name "C_HS_C") (class "Default")
      (node (ref "U1") (pin "46") (pinfunction "PWM_WY1_H_46") (pintype "output"))
      (node (ref "U3") (pin "2") (pinfunction "HI_2") (pintype "input"))
    )
    (net (code "23") (name "C_HS_D") (class "Default")
      (node (ref "U1") (pin "48") (pinfunction "PWM_Y2_H_48") (pintype "output"))
      (node (ref "U2") (pin "2") (pinfunction "HI_2") (pintype "input"))
    )
    (net (code "24") (name "C_LS_A") (class "Default")
      (node (ref "U1") (pin "40") (pinfunction "PWM_UX1_L_40") (pintype "output"))
      (node (ref "U5") (pin "3") (pinfunction "LI_3") (pintype "input"))
    )
    (net (code "25") (name "C_LS_B") (class "Default")
      (node (ref "U1") (pin "42") (pinfunction "PWM_VX2_L_42") (pintype "output"))
      (node (ref "U4") (pin "3") (pinfunction "LI_3") (pintype "input"))
    )
    (net (code "26") (name "C_LS_C") (class "Default")
      (node (ref "U1") (pin "47") (pinfunction "PWM_WY1_L_47") (pintype "output"))
      (node (ref "U3") (pin "3") (pinfunction "LI_3") (pintype "input"))
    )
    (net (code "27") (name "C_LS_D") (class "Default")
      (node (ref "U1") (pin "49") (pinfunction "PWM_Y2_L_49") (pintype "output"))
      (node (ref "U2") (pin "3") (pinfunction "LI_3") (pintype "input"))
    )
    (net (code "28") (name "DIR") (class "Default")
      (node (ref "JP10") (pin "3") (pinfunction "3_3") (pintype "passive"))
      (node (ref "U1") (pin "56") (pinfunction "DIR_56") (pintype "input"))
    )
    (net (code "29") (name "ENABLE") (class "Default")
      (node (ref "JP7") (pin "2") (pinfunction "2_2") (pintype "passive"))
      (node (ref "R31") (pin "1") (pinfunction "1_1") (pintype "passive"))
      (node (ref "U1") (pin "55") (pinfunction "ENI_55") (pintype "input"))
    )
    (net (code "30") (name "ENC2_A") (class "Default")
      (node (ref "JP9") (pin "2") (pinfunction "2_2") (pintype "passive"))
      (node (ref "U1") (pin "64") (pinfunction "ENC2_A_64") (pintype "input"))
    )
    (net (code "31") (name "ENC2_B") (class "Default")
      (node (ref "JP9") (pin "4") (pinfunction "4_4") (pintype "passive"))
      (node (ref "U1") (pin "65") (pinfunction "ENC2_B_65") (pintype "input"))
    )
    (net (code "32") (name "ENC2_Z") (class "Default")
      (node (ref "JP9") (pin "6") (pinfunction "6_6") (pintype "passive"))
      (node (ref "U1") (pin "66") (pinfunction "ENC2_N_66") (pintype "input"))
    )
    (net (code "33") (name "ENC_A") (class "Default")
      (node (ref "U1") (pin "35") (pinfunction "ENC_A_35") (pintype "input"))
      (node (ref "U18") (pin "P$2") (pinfunction "3Y_P$2") (pintype "bidirectional"))
    )
    (net (code "34") (name "ENC_A_5V") (class "Default")
      (node (ref "C36") (pin "2") (pinfunction "2_2") (pintype "passive"))
      (node (ref "R46") (pin "1") (pinfunction "1_1") (pintype "passive"))
      (node (ref "U18") (pin "P$6") (pinfunction "3A_P$6") (pintype "bidirectional"))
    )
    (net (code "35") (name "ENC_B") (class "Default")
      (node (ref "U1") (pin "34") (pinfunction "ENC_B_34") (pintype "input"))
      (node (ref "U18") (pin "P$5") (pinfunction "2Y_P$5") (pintype "bidirectional"))
    )
    (net (code "36") (name "ENC_B_5V") (class "Default")
      (node (ref "C34") (pin "2") (pinfunction "2_2") (pintype "passive"))
      (node (ref "R45") (pin "1") (pinfunction "1_1") (pintype "passive"))
      (node (ref "U18") (pin "P$3") (pinfunction "2A_P$3") (pintype "bidirectional"))
    )
    (net (code "37") (name "ENC_Z") (class "Default")
      (node (ref "U1") (pin "33") (pinfunction "ENC_N_33") (pintype "input"))
      (node (ref "U18") (pin "P$7") (pinfunction "1Y_P$7") (pintype "bidirectional"))
    )
    (net (code "38") (name "ENC_Z_5V") (class "Default")
      (node (ref "C32") (pin "2") (pinfunction "2_2") (pintype "passive"))
      (node (ref "R44") (pin "1") (pinfunction "1_1") (pintype "passive"))
      (node (ref "U18") (pin "P$1") (pinfunction "1A_P$1") (pintype "bidirectional"))
    )
    (net (code "39") (name "ENO") (class "Default")
      (node (ref "JP1") (pin "1") (pinfunction "1_1") (pintype "passive"))
      (node (ref "U1") (pin "32") (pinfunction "ENO_32") (pintype "output"))
    )
    (net (code "40") (name "FLAG") (class "Default")
      (node (ref "D1") (pin "C") (pinfunction "C_C") (pintype "passive"))
      (node (ref "R4") (pin "2") (pinfunction "2_2") (pintype "passive"))
      (node (ref "X1") (pin "11") (pinfunction "KL_11") (pintype "passive"))
    )
    (net (code "41") (name "GND") (class "Default")
      (node (ref "C1") (pin "1") (pinfunction "1_1") (pintype "passive"))
      (node (ref "C10") (pin "1") (pinfunction "1_1") (pintype "passive"))
      (node (ref "C11") (pin "-") (pinfunction "-_-") (pintype "passive"))
      (node (ref "C12") (pin "-") (pinfunction "-_-") (pintype "passive"))
      (node (ref "C13") (pin "2") (pinfunction "2_2") (pintype "passive"))
      (node (ref "C14") (pin "2") (pinfunction "2_2") (pintype "passive"))
      (node (ref "C15") (pin "2") (pinfunction "2_2") (pintype "passive"))
      (node (ref "C16") (pin "2") (pinfunction "2_2") (pintype "passive"))
      (node (ref "C17") (pin "2") (pinfunction "2_2") (pintype "passive"))
      (node (ref "C18") (pin "2") (pinfunction "2_2") (pintype "passive"))
      (node (ref "C19") (pin "2") (pinfunction "2_2") (pintype "passive"))
      (node (ref "C2") (pin "1") (pinfunction "1_1") (pintype "passive"))
      (node (ref "C20") (pin "2") (pinfunction "2_2") (pintype "passive"))
      (node (ref "C25") (pin "2") (pinfunction "2_2") (pintype "passive"))
      (node (ref "C26") (pin "2") (pinfunction "2_2") (pintype "passive"))
      (node (ref "C27") (pin "2") (pinfunction "2_2") (pintype "passive"))
      (node (ref "C28") (pin "2") (pinfunction "2_2") (pintype "passive"))
      (node (ref "C29") (pin "-") (pinfunction "-_-") (pintype "passive"))
      (node (ref "C3") (pin "1") (pinfunction "1_1") (pintype "passive"))
      (node (ref "C30") (pin "1") (pinfunction "1_1") (pintype "passive"))
      (node (ref "C31") (pin "1") (pinfunction "1_1") (pintype "passive"))
      (node (ref "C32") (pin "1") (pinfunction "1_1") (pintype "passive"))
      (node (ref "C33") (pin "1") (pinfunction "1_1") (pintype "passive"))
      (node (ref "C34") (pin "1") (pinfunction "1_1") (pintype "passive"))
      (node (ref "C35") (pin "1") (pinfunction "1_1") (pintype "passive"))
      (node (ref "C36") (pin "1") (pinfunction "1_1") (pintype "passive"))
      (node (ref "C37") (pin "1") (pinfunction "1_1") (pintype "passive"))
      (node (ref "C38") (pin "2") (pinfunction "2_2") (pintype "passive"))
      (node (ref "C4") (pin "1") (pinfunction "1_1") (pintype "passive"))
      (node (ref "C40") (pin "2") (pinfunction "2_2") (pintype "passive"))
      (node (ref "C41") (pin "1") (pinfunction "1_1") (pintype "passive"))
      (node (ref "C43") (pin "1") (pinfunction "1_1") (pintype "passive"))
      (node (ref "C44") (pin "2") (pinfunction "2_2") (pintype "passive"))
      (node (ref "C45") (pin "2") (pinfunction "2_2") (pintype "passive"))
      (node (ref "C5") (pin "1") (pinfunction "1_1") (pintype "passive"))
      (node (ref "C6") (pin "1") (pinfunction "1_1") (pintype "passive"))
      (node (ref "C7") (pin "1") (pinfunction "1_1") (pintype "passive"))
      (node (ref "C8") (pin "1") (pinfunction "1_1") (pintype "passive"))
      (node (ref "C9") (pin "1") (pinfunction "1_1") (pintype "passive"))
      (node (ref "D12") (pin "A") (pinfunction "A_A") (pintype "passive"))
      (node (ref "D13") (pin "A") (pinfunction "A_A") (pintype "passive"))
      (node (ref "D15") (pin "A") (pinfunction "A_A") (pintype "passive"))
      (node (ref "H1") (pin "B3,0") (pinfunction "MOUNT_B3,0") (pintype "passive"))
      (node (ref "H2") (pin "B3,0") (pinfunction "MOUNT_B3,0") (pintype "passive"))
      (node (ref "H3") (pin "B3,0") (pinfunction "MOUNT_B3,0") (pintype "passive"))
      (node (ref "H4") (pin "B3,0") (pinfunction "MOUNT_B3,0") (pintype "passive"))
      (node (ref "H5") (pin "B3,0") (pinfunction "MOUNT_B3,0") (pintype "passive"))
      (node (ref "H6") (pin "B3,0") (pinfunction "MOUNT_B3,0") (pintype "passive"))
      (node (ref "JP11") (pin "5") (pinfunction "5_5") (pintype "passive"))
      (node (ref "JP12") (pin "5") (pinfunction "5_5") (pintype "passive"))
      (node (ref "JP2") (pin "1") (pinfunction "1_1") (pintype "passive"))
      (node (ref "JP6") (pin "3") (pinfunction "3_3") (pintype "passive"))
      (node (ref "JP7") (pin "1") (pinfunction "1_1") (pintype "passive"))
      (node (ref "LED1") (pin "C") (pinfunction "C_C") (pintype "passive"))
      (node (ref "R14") (pin "1") (pinfunction "1_1") (pintype "passive"))
      (node (ref "R16") (pin "1") (pinfunction "1_1") (pintype "passive"))
      (node (ref "R17") (pin "1") (pinfunction "1_1") (pintype "passive"))
      (node (ref "R19") (pin "1") (pinfunction "1_1") (pintype "passive"))
      (node (ref "R2") (pin "1") (pinfunction "1_1") (pintype "passive"))
      (node (ref "R20") (pin "1") (pinfunction "1_1") (pintype "passive"))
      (node (ref "R25") (pin "1") (pinfunction "1_1") (pintype "passive"))
      (node (ref "R26") (pin "1") (pinfunction "1_1") (pintype "passive"))
      (node (ref "R28") (pin "1") (pinfunction "1_1") (pintype "passive"))
      (node (ref "R30") (pin "1") (pinfunction "1_1") (pintype "passive"))
      (node (ref "R33") (pin "1") (pinfunction "1_1") (pintype "passive"))
      (node (ref "R4") (pin "1") (pinfunction "1_1") (pintype "passive"))
      (node (ref "R48") (pin "2") (pinfunction "2_2") (pintype "passive"))
      (node (ref "R50") (pin "1") (pinfunction "1_1") (pintype "passive"))
      (node (ref "R51") (pin "1") (pinfunction "1_1") (pintype "passive"))
      (node (ref "U1") (pin "14") (pinfunction "GNDIO2_14") (pintype "power_in"))
      (node (ref "U1") (pin "24") (pinfunction "GNDA_24") (pintype "power_in"))
      (node (ref "U1") (pin "3") (pinfunction "GNDIO1_3") (pintype "power_in"))
      (node (ref "U1") (pin "44") (pinfunction "GNDIO3_44") (pintype "power_in"))
      (node (ref "U1") (pin "53") (pinfunction "GNDIO4_53") (pintype "power_in"))
      (node (ref "U1") (pin "54") (pinfunction "TEST_54") (pintype "input"))
      (node (ref "U1") (pin "59") (pinfunction "PWM_IDLE_H_59") (pintype "input"))
      (node (ref "U1") (pin "60") (pinfunction "PWM_IDLE_L_60") (pintype "input"))
      (node (ref "U1") (pin "62") (pinfunction "GNDIO5_62") (pintype "power_in"))
      (node (ref "U1") (pin "73") (pinfunction "GNDIO6_73") (pintype "power_in"))
      (node (ref "U1") (pin "77") (pinfunction "GNDIO6_77") (pintype "power_in"))
      (node (ref "U11") (pin "1") (pinfunction "S_1") (pintype "passive"))
      (node (ref "U11") (pin "2") (pinfunction "S_2") (pintype "passive"))
      (node (ref "U11") (pin "3") (pinfunction "S_3") (pintype "passive"))
      (node (ref "U13") (pin "1") (pinfunction "S_1") (pintype "passive"))
      (node (ref "U13") (pin "2") (pinfunction "S_2") (pintype "passive"))
      (node (ref "U13") (pin "3") (pinfunction "S_3") (pintype "passive"))
      (node (ref "U14") (pin "1") (pinfunction "GND_1") (pintype "bidirectional"))
      (node (ref "U14") (pin "4") (pinfunction "GND_4") (pintype "bidirectional"))
      (node (ref "U16") (pin "1") (pinfunction "S_1") (pintype "passive"))
      (node (ref "U16") (pin "2") (pinfunction "S_2") (pintype "passive"))
      (node (ref "U16") (pin "3") (pinfunction "S_3") (pintype "passive"))
      (node (ref "U17") (pin "1") (pinfunction "S_1") (pintype "passive"))
      (node (ref "U17") (pin "2") (pinfunction "S_2") (pintype "passive"))
      (node (ref "U17") (pin "3") (pinfunction "S_3") (pintype "passive"))
      (node (ref "U18") (pin "P$4") (pinfunction "GND_P$4") (pintype "bidirectional"))
      (node (ref "U19") (pin "P$4") (pinfunction "GND_P$4") (pintype "bidirectional"))
      (node (ref "U2") (pin "4") (pinfunction "VSS_4") (pintype "power_in"))
      (node (ref "U2") (pin "9") (pinfunction "EP_9") (pintype "power_in"))
      (node (ref "U20") (pin "2") (pinfunction "GND_2") (pintype "bidirectional"))
      (node (ref "U21") (pin "1") (pinfunction "ADJ_1") (pintype "input"))
      (node (ref "U23") (pin "3") (pinfunction "SGND_3") (pintype "power_in"))
      (node (ref "U23") (pin "6") (pinfunction "GND_6") (pintype "power_in"))
      (node (ref "U24") (pin "2") (pinfunction "GND_2") (pintype "bidirectional"))
      (node (ref "U3") (pin "4") (pinfunction "VSS_4") (pintype "power_in"))
      (node (ref "U3") (pin "9") (pinfunction "EP_9") (pintype "power_in"))
      (node (ref "U4") (pin "4") (pinfunction "VSS_4") (pintype "power_in"))
      (node (ref "U4") (pin "9") (pinfunction "EP_9") (pintype "power_in"))
      (node (ref "U5") (pin "4") (pinfunction "VSS_4") (pintype "power_in"))
      (node (ref "U5") (pin "9") (pinfunction "EP_9") (pintype "power_in"))
      (node (ref "U7") (pin "1") (pinfunction "S_1") (pintype "passive"))
      (node (ref "U7") (pin "2") (pinfunction "S_2") (pintype "passive"))
      (node (ref "U7") (pin "3") (pinfunction "S_3") (pintype "passive"))
      (node (ref "U8") (pin "2") (pinfunction "GND_2") (pintype "bidirectional"))
      (node (ref "U9") (pin "2") (pinfunction "GND_2") (pintype "bidirectional"))
      (node (ref "X1") (pin "1") (pinfunction "KL_1") (pintype "passive"))
      (node (ref "X2") (pin "1") (pinfunction "1_1") (pintype "passive"))
      (node (ref "Y1") (pin "2") (pinfunction "GND_2") (pintype "power_in"))
    )
    (net (code "42") (name "GPIO0") (class "Default")
      (node (ref "JP8") (pin "1") (pinfunction "1_1") (pintype "passive"))
      (node (ref "U1") (pin "70") (pinfunction "GPIO0/ADC_I0_MCD_70") (pintype "bidirectional"))
    )
    (net (code "43") (name "GPIO1") (class "Default")
      (node (ref "JP8") (pin "2") (pinfunction "2_2") (pintype "passive"))
      (node (ref "U1") (pin "71") (pinfunction "GPIO1/ADC_I1_MCD_71") (pintype "bidirectional"))
    )
    (net (code "44") (name "GPIO2") (class "Default")
      (node (ref "JP8") (pin "3") (pinfunction "3_3") (pintype "passive"))
      (node (ref "U1") (pin "74") (pinfunction "GPIO2/ADC_VM_MCD_74") (pintype "bidirectional"))
    )
    (net (code "45") (name "GPIO3") (class "Default")
      (node (ref "JP8") (pin "4") (pinfunction "4_4") (pintype "passive"))
      (node (ref "U1") (pin "75") (pinfunction "GPIO3/AGPI_A_MCD/DBGSPI_NSCS_75") (pintype "bidirectional"))
    )
    (net (code "46") (name "GPIO4") (class "Default")
      (node (ref "JP8") (pin "5") (pinfunction "5_5") (pintype "passive"))
      (node (ref "U1") (pin "76") (pinfunction "GPIO4/AGPI_B_MCD/DBGSPI_SCK_76") (pintype "bidirectional"))
    )
    (net (code "47") (name "GPIO5") (class "Default")
      (node (ref "JP8") (pin "6") (pinfunction "6_6") (pintype "passive"))
      (node (ref "U1") (pin "1") (pinfunction "GPIO5/AENC_UX_MCD/DBGSPI_MOSI_1") (pintype "bidirectional"))
    )
    (net (code "48") (name "GPIO6") (class "Default")
      (node (ref "JP8") (pin "7") (pinfunction "7_7") (pintype "passive"))
      (node (ref "U1") (pin "4") (pinfunction "GPIO6/AENC_VN_MCD/DBGSPI_MISO_4") (pintype "bidirectional"))
    )
    (net (code "49") (name "GPIO7") (class "Default")
      (node (ref "JP8") (pin "8") (pinfunction "8_8") (pintype "passive"))
      (node (ref "U1") (pin "5") (pinfunction "GPIO7/AENC_WY_MCD/DBGSPI_TRG_5") (pintype "bidirectional"))
    )
    (net (code "50") (name "G_HS_A") (class "Default")
      (node (ref "D6") (pin "C") (pinfunction "C_C") (pintype "passive"))
      (node (ref "R11") (pin "1") (pinfunction "1_1") (pintype "passive"))
      (node (ref "U6") (pin "4") (pinfunction "G_4") (pintype "passive"))
    )
    (net (code "51") (name "G_HS_B") (class "Default")
      (node (ref "D7") (pin "C") (pinfunction "C_C") (pintype "passive"))
      (node (ref "R9") (pin "1") (pinfunction "1_1") (pintype "passive"))
      (node (ref "U10") (pin "4") (pinfunction "G_4") (pintype "passive"))
    )
    (net (code "52") (name "G_HS_C") (class "Default")
      (node (ref "D8") (pin "C") (pinfunction "C_C") (pintype "passive"))
      (node (ref "R7") (pin "1") (pinfunction "1_1") (pintype "passive"))
      (node (ref "U12") (pin "4") (pinfunction "G_4") (pintype "passive"))
    )
    (net (code "53") (name "G_HS_D") (class "Default")
      (node (ref "D10") (pin "C") (pinfunction "C_C") (pintype "passive"))
      (node (ref "R5") (pin "1") (pinfunction "1_1") (pintype "passive"))
      (node (ref "U15") (pin "4") (pinfunction "G_4") (pintype "passive"))
    )
    (net (code "54") (name "G_LS_A") (class "Default")
      (node (ref "R12") (pin "1") (pinfunction "1_1") (pintype "passive"))
      (node (ref "R17") (pin "2") (pinfunction "2_2") (pintype "passive"))
      (node (ref "U7") (pin "4") (pinfunction "G_4") (pintype "passive"))
    )
    (net (code "55") (name "G_LS_B") (class "Default")
      (node (ref "R10") (pin "1") (pinfunction "1_1") (pintype "passive"))
      (node (ref "R20") (pin "2") (pinfunction "2_2") (pintype "passive"))
      (node (ref "U11") (pin "4") (pinfunction "G_4") (pintype "passive"))
    )
    (net (code "56") (name "G_LS_C") (class "Default")
      (node (ref "R25") (pin "2") (pinfunction "2_2") (pintype "passive"))
      (node (ref "R8") (pin "1") (pinfunction "1_1") (pintype "passive"))
      (node (ref "U13") (pin "4") (pinfunction "G_4") (pintype "passive"))
    )
    (net (code "57") (name "G_LS_D") (class "Default")
      (node (ref "R28") (pin "2") (pinfunction "2_2") (pintype "passive"))
      (node (ref "R6") (pin "1") (pinfunction "1_1") (pintype "passive"))
      (node (ref "U16") (pin "4") (pinfunction "G_4") (pintype "passive"))
    )
    (net (code "58") (name "HALL_UX") (class "Default")
      (node (ref "U1") (pin "38") (pinfunction "HALL_UX_38") (pintype "input"))
      (node (ref "U19") (pin "P$2") (pinfunction "3Y_P$2") (pintype "bidirectional"))
    )
    (net (code "59") (name "HALL_UX_5V") (class "Default")
      (node (ref "C33") (pin "2") (pinfunction "2_2") (pintype "passive"))
      (node (ref "R41") (pin "1") (pinfunction "1_1") (pintype "passive"))
      (node (ref "U19") (pin "P$6") (pinfunction "3A_P$6") (pintype "bidirectional"))
    )
    (net (code "60") (name "HALL_V") (class "Default")
      (node (ref "U1") (pin "37") (pinfunction "HALL_V_37") (pintype "input"))
      (node (ref "U19") (pin "P$5") (pinfunction "2Y_P$5") (pintype "bidirectional"))
    )
    (net (code "61") (name "HALL_V_5V") (class "Default")
      (node (ref "C35") (pin "2") (pinfunction "2_2") (pintype "passive"))
      (node (ref "R42") (pin "1") (pinfunction "1_1") (pintype "passive"))
      (node (ref "U19") (pin "P$3") (pinfunction "2A_P$3") (pintype "bidirectional"))
    )
    (net (code "62") (name "HALL_WY") (class "Default")
      (node (ref "U1") (pin "36") (pinfunction "HALL_WY_36") (pintype "input"))
      (node (ref "U19") (pin "P$7") (pinfunction "1Y_P$7") (pintype "bidirectional"))
    )
    (net (code "63") (name "HALL_WY_5V") (class "Default")
      (node (ref "C37") (pin "2") (pinfunction "2_2") (pintype "passive"))
      (node (ref "R43") (pin "1") (pinfunction "1_1") (pintype "passive"))
      (node (ref "U19") (pin "P$1") (pinfunction "1A_P$1") (pintype "bidirectional"))
    )
    (net (code "64") (name "INPUT_GATE") (class "Default")
      (node (ref "U20") (pin "5") (pinfunction "GATE_5") (pintype "bidirectional"))
      (node (ref "U22") (pin "4") (pinfunction "G_4") (pintype "passive"))
    )
    (net (code "65") (name "MISO") (class "Default")
      (node (ref "U1") (pin "9") (pinfunction "SPI_MISO_9") (pintype "output"))
      (node (ref "X1") (pin "6") (pinfunction "KL_6") (pintype "passive"))
    )
    (net (code "66") (name "MOSI") (class "Default")
      (node (ref "U1") (pin "8") (pinfunction "SPI_MOSI_8") (pintype "input"))
      (node (ref "X1") (pin "5") (pinfunction "KL_5") (pintype "passive"))
    )
    (net (code "67") (name "MOT_A") (class "Default")
      (node (ref "C24") (pin "2") (pinfunction "2_2") (pintype "passive"))
      (node (ref "D6") (pin "A") (pinfunction "A_A") (pintype "passive"))
      (node (ref "R22") (pin "2") (pinfunction "2_2") (pintype "passive"))
      (node (ref "U5") (pin "6") (pinfunction "HS_6") (pintype "input"))
      (node (ref "U6") (pin "1") (pinfunction "S_1") (pintype "passive"))
      (node (ref "U6") (pin "2") (pinfunction "S_2") (pintype "passive"))
      (node (ref "U6") (pin "3") (pinfunction "S_3") (pintype "passive"))
      (node (ref "U7") (pin "5") (pinfunction "D_5") (pintype "passive"))
      (node (ref "U8") (pin "8") (pinfunction "IN+_8") (pintype "bidirectional"))
    )
    (net (code "68") (name "MOT_A_OUT") (class "Default")
      (node (ref "R22") (pin "1") (pinfunction "1_1") (pintype "passive"))
      (node (ref "U8") (pin "1") (pinfunction "IN-_1") (pintype "bidirectional"))
      (node (ref "X3") (pin "1") (pinfunction "1_1") (pintype "passive"))
    )
    (net (code "69") (name "MOT_B") (class "Default")
      (node (ref "C23") (pin "2") (pinfunction "2_2") (pintype "passive"))
      (node (ref "D7") (pin "A") (pinfunction "A_A") (pintype "passive"))
      (node (ref "U10") (pin "1") (pinfunction "S_1") (pintype "passive"))
      (node (ref "U10") (pin "2") (pinfunction "S_2") (pintype "passive"))
      (node (ref "U10") (pin "3") (pinfunction "S_3") (pintype "passive"))
      (node (ref "U11") (pin "5") (pinfunction "D_5") (pintype "passive"))
      (node (ref "U4") (pin "6") (pinfunction "HS_6") (pintype "input"))
      (node (ref "X3") (pin "2") (pinfunction "1_2") (pintype "passive"))
    )
    (net (code "70") (name "MOT_C") (class "Default")
      (node (ref "C22") (pin "2") (pinfunction "2_2") (pintype "passive"))
      (node (ref "D8") (pin "A") (pinfunction "A_A") (pintype "passive"))
      (node (ref "R21") (pin "2") (pinfunction "2_2") (pintype "passive"))
      (node (ref "U12") (pin "1") (pinfunction "S_1") (pintype "passive"))
      (node (ref "U12") (pin "2") (pinfunction "S_2") (pintype "passive"))
      (node (ref "U12") (pin "3") (pinfunction "S_3") (pintype "passive"))
      (node (ref "U13") (pin "5") (pinfunction "D_5") (pintype "passive"))
      (node (ref "U3") (pin "6") (pinfunction "HS_6") (pintype "input"))
      (node (ref "U9") (pin "8") (pinfunction "IN+_8") (pintype "bidirectional"))
    )
    (net (code "71") (name "MOT_C_OUT") (class "Default")
      (node (ref "R21") (pin "1") (pinfunction "1_1") (pintype "passive"))
      (node (ref "U9") (pin "1") (pinfunction "IN-_1") (pintype "bidirectional"))
      (node (ref "X3") (pin "3") (pinfunction "1_3") (pintype "passive"))
    )
    (net (code "72") (name "MOT_D") (class "Default")
      (node (ref "C21") (pin "2") (pinfunction "2_2") (pintype "passive"))
      (node (ref "D10") (pin "A") (pinfunction "A_A") (pintype "passive"))
      (node (ref "U15") (pin "1") (pinfunction "S_1") (pintype "passive"))
      (node (ref "U15") (pin "2") (pinfunction "S_2") (pintype "passive"))
      (node (ref "U15") (pin "3") (pinfunction "S_3") (pintype "passive"))
      (node (ref "U16") (pin "5") (pinfunction "D_5") (pintype "passive"))
      (node (ref "U2") (pin "6") (pinfunction "HS_6") (pintype "input"))
      (node (ref "X3") (pin "4") (pinfunction "1_4") (pintype "passive"))
    )
    (net (code "73") (name "Net-(JP3-Pad2)") (class "Default")
      (node (ref "JP3") (pin "2") (pinfunction "2_2") (pintype "passive"))
      (node (ref "JP3") (pin "4") (pinfunction "4_4") (pintype "passive"))
      (node (ref "JP3") (pin "6") (pinfunction "6_6") (pintype "passive"))
      (node (ref "R32") (pin "1") (pinfunction "1_1") (pintype "passive"))
      (node (ref "R33") (pin "2") (pinfunction "2_2") (pintype "passive"))
    )
    (net (code "74") (name "Net-(JP11-Pad2)") (class "Default")
      (node (ref "JP11") (pin "2") (pinfunction "2_2") (pintype "passive"))
      (node (ref "R35") (pin "1") (pinfunction "1_1") (pintype "passive"))
      (node (ref "R44") (pin "2") (pinfunction "2_2") (pintype "passive"))
    )
    (net (code "75") (name "Net-(JP11-Pad3)") (class "Default")
      (node (ref "JP11") (pin "3") (pinfunction "3_3") (pintype "passive"))
      (node (ref "R36") (pin "1") (pinfunction "1_1") (pintype "passive"))
      (node (ref "R45") (pin "2") (pinfunction "2_2") (pintype "passive"))
    )
    (net (code "76") (name "Net-(JP11-Pad4)") (class "Default")
      (node (ref "JP11") (pin "4") (pinfunction "4_4") (pintype "passive"))
      (node (ref "R38") (pin "1") (pinfunction "1_1") (pintype "passive"))
      (node (ref "R46") (pin "2") (pinfunction "2_2") (pintype "passive"))
    )
    (net (code "77") (name "Net-(JP12-Pad2)") (class "Default")
      (node (ref "JP12") (pin "2") (pinfunction "2_2") (pintype "passive"))
      (node (ref "R40") (pin "1") (pinfunction "1_1") (pintype "passive"))
      (node (ref "R43") (pin "2") (pinfunction "2_2") (pintype "passive"))
    )
    (net (code "78") (name "Net-(JP12-Pad3)") (class "Default")
      (node (ref "JP12") (pin "3") (pinfunction "3_3") (pintype "passive"))
      (node (ref "R39") (pin "1") (pinfunction "1_1") (pintype "passive"))
      (node (ref "R42") (pin "2") (pinfunction "2_2") (pintype "passive"))
    )
    (net (code "79") (name "Net-(JP12-Pad4)") (class "Default")
      (node (ref "JP12") (pin "4") (pinfunction "4_4") (pintype "passive"))
      (node (ref "R37") (pin "1") (pinfunction "1_1") (pintype "passive"))
      (node (ref "R41") (pin "2") (pinfunction "2_2") (pintype "passive"))
    )
    (net (code "80") (name "Net-(LED1-PadA)") (class "Default")
      (node (ref "LED1") (pin "A") (pinfunction "A_A") (pintype "passive"))
      (node (ref "R34") (pin "1") (pinfunction "1_1") (pintype "passive"))
    )
    (net (code "81") (name "Net-(U1B-STATUS)") (class "Default")
      (node (ref "D1") (pin "A") (pinfunction "A_A") (pintype "passive"))
      (node (ref "U1") (pin "12") (pinfunction "STATUS_12") (pintype "output"))
    )
    (net (code "82") (name "Net-(U1B-VCCCORE1)") (class "Default")
      (node (ref "C3") (pin "2") (pinfunction "2_2") (pintype "passive"))
      (node (ref "C5") (pin "2") (pinfunction "2_2") (pintype "passive"))
      (node (ref "C6") (pin "2") (pinfunction "2_2") (pintype "passive"))
      (node (ref "U1") (pin "15") (pinfunction "VCCCORE1_15") (pintype "power_in"))
      (node (ref "U1") (pin "45") (pinfunction "VCCCORE2_45") (pintype "power_in"))
      (node (ref "U1") (pin "63") (pinfunction "VCCCORE3_63") (pintype "power_in"))
    )
    (net (code "83") (name "Net-(U2-HB)") (class "Default")
      (node (ref "C21") (pin "1") (pinfunction "1_1") (pintype "passive"))
      (node (ref "D2") (pin "C") (pinfunction "C_C") (pintype "passive"))
      (node (ref "U2") (pin "8") (pinfunction "HB_8") (pintype "input"))
    )
    (net (code "84") (name "Net-(U2-HO)") (class "Default")
      (node (ref "R5") (pin "2") (pinfunction "2_2") (pintype "passive"))
      (node (ref "U2") (pin "7") (pinfunction "HO_7") (pintype "output"))
    )
    (net (code "85") (name "Net-(U2-LO)") (class "Default")
      (node (ref "R6") (pin "2") (pinfunction "2_2") (pintype "passive"))
      (node (ref "U2") (pin "5") (pinfunction "LO_5") (pintype "output"))
    )
    (net (code "86") (name "Net-(U3-HB)") (class "Default")
      (node (ref "C22") (pin "1") (pinfunction "1_1") (pintype "passive"))
      (node (ref "D3") (pin "C") (pinfunction "C_C") (pintype "passive"))
      (node (ref "U3") (pin "8") (pinfunction "HB_8") (pintype "input"))
    )
    (net (code "87") (name "Net-(U3-HO)") (class "Default")
      (node (ref "R7") (pin "2") (pinfunction "2_2") (pintype "passive"))
      (node (ref "U3") (pin "7") (pinfunction "HO_7") (pintype "output"))
    )
    (net (code "88") (name "Net-(U3-LO)") (class "Default")
      (node (ref "R8") (pin "2") (pinfunction "2_2") (pintype "passive"))
      (node (ref "U3") (pin "5") (pinfunction "LO_5") (pintype "output"))
    )
    (net (code "89") (name "Net-(U4-HB)") (class "Default")
      (node (ref "C23") (pin "1") (pinfunction "1_1") (pintype "passive"))
      (node (ref "D4") (pin "C") (pinfunction "C_C") (pintype "passive"))
      (node (ref "U4") (pin "8") (pinfunction "HB_8") (pintype "input"))
    )
    (net (code "90") (name "Net-(U4-HO)") (class "Default")
      (node (ref "R9") (pin "2") (pinfunction "2_2") (pintype "passive"))
      (node (ref "U4") (pin "7") (pinfunction "HO_7") (pintype "output"))
    )
    (net (code "91") (name "Net-(U4-LO)") (class "Default")
      (node (ref "R10") (pin "2") (pinfunction "2_2") (pintype "passive"))
      (node (ref "U4") (pin "5") (pinfunction "LO_5") (pintype "output"))
    )
    (net (code "92") (name "Net-(U5-HB)") (class "Default")
      (node (ref "C24") (pin "1") (pinfunction "1_1") (pintype "passive"))
      (node (ref "D5") (pin "C") (pinfunction "C_C") (pintype "passive"))
      (node (ref "U5") (pin "8") (pinfunction "HB_8") (pintype "input"))
    )
    (net (code "93") (name "Net-(U5-HO)") (class "Default")
      (node (ref "R11") (pin "2") (pinfunction "2_2") (pintype "passive"))
      (node (ref "U5") (pin "7") (pinfunction "HO_7") (pintype "output"))
    )
    (net (code "94") (name "Net-(U5-LO)") (class "Default")
      (node (ref "R12") (pin "2") (pinfunction "2_2") (pintype "passive"))
      (node (ref "U5") (pin "5") (pinfunction "LO_5") (pintype "output"))
    )
    (net (code "95") (name "Net-(U8-OUT)") (class "Default")
      (node (ref "R23") (pin "2") (pinfunction "2_2") (pintype "passive"))
      (node (ref "U8") (pin "5") (pinfunction "OUT_5") (pintype "bidirectional"))
    )
    (net (code "96") (name "Net-(U9-OUT)") (class "Default")
      (node (ref "R24") (pin "2") (pinfunction "2_2") (pintype "passive"))
      (node (ref "U9") (pin "5") (pinfunction "OUT_5") (pintype "bidirectional"))
    )
    (net (code "97") (name "Net-(U20-VCAP)") (class "Default")
      (node (ref "C39") (pin "1") (pinfunction "1_1") (pintype "passive"))
      (node (ref "U20") (pin "1") (pinfunction "VCAP_1") (pintype "bidirectional"))
    )
    (net (code "98") (name "Net-(U23-BST)") (class "Default")
      (node (ref "C42") (pin "1") (pinfunction "1_1") (pintype "passive"))
      (node (ref "U23") (pin "1") (pinfunction "BST_1") (pintype "passive"))
    )
    (net (code "99") (name "Net-(U23-LX)") (class "Default")
      (node (ref "C42") (pin "2") (pinfunction "2_2") (pintype "passive"))
      (node (ref "D12") (pin "C") (pinfunction "C_C") (pintype "passive"))
      (node (ref "L1") (pin "1") (pinfunction "1_1") (pintype "passive"))
      (node (ref "U23") (pin "8") (pinfunction "LX_8") (pintype "passive"))
    )
    (net (code "100") (name "Net-(U23-ON{slash}~{OFF})") (class "Default")
      (node (ref "R47") (pin "1") (pinfunction "1_1") (pintype "passive"))
      (node (ref "R48") (pin "1") (pinfunction "1_1") (pintype "passive"))
      (node (ref "U23") (pin "5") (pinfunction "ON/~{OFF}_5") (pintype "input"))
    )
    (net (code "101") (name "Net-(U23-VD)") (class "Default")
      (node (ref "C41") (pin "2") (pinfunction "2_2") (pintype "passive"))
      (node (ref "U23") (pin "2") (pinfunction "VD_2") (pintype "power_in"))
    )
    (net (code "102") (name "Net-(U24-FB)") (class "Default")
      (node (ref "R49") (pin "1") (pinfunction "1_1") (pintype "passive"))
      (node (ref "R50") (pin "2") (pinfunction "2_2") (pintype "passive"))
      (node (ref "U24") (pin "3") (pinfunction "FB_3") (pintype "bidirectional"))
    )
    (net (code "103") (name "Net-(U24-SW)") (class "Default")
      (node (ref "D14") (pin "A") (pinfunction "A_A") (pintype "passive"))
      (node (ref "L2") (pin "2") (pinfunction "2_2") (pintype "passive"))
      (node (ref "U24") (pin "1") (pinfunction "SW_1") (pintype "bidirectional"))
    )
    (net (code "104") (name "Net-(X1H-KL)") (class "Default")
      (node (ref "R31") (pin "2") (pinfunction "2_2") (pintype "passive"))
      (node (ref "X1") (pin "16") (pinfunction "KL_16") (pintype "passive"))
    )
    (net (code "105") (name "Net-(X1I-KL)") (class "Default")
      (node (ref "JP5") (pin "1") (pinfunction "1_1") (pintype "passive"))
      (node (ref "X1") (pin "2") (pinfunction "KL_2") (pintype "passive"))
    )
    (net (code "106") (name "Net-(X1K-KL)") (class "Default")
      (node (ref "SJ4") (pin "1") (pinfunction "1_1") (pintype "passive"))
      (node (ref "X1") (pin "4") (pinfunction "KL_4") (pintype "passive"))
    )
    (net (code "107") (name "PWM_I") (class "Default")
      (node (ref "JP10") (pin "1") (pinfunction "1_1") (pintype "passive"))
      (node (ref "U1") (pin "58") (pinfunction "PWM_I_58") (pintype "input"))
    )
    (net (code "108") (name "REF_H") (class "Default")
      (node (ref "JP9") (pin "3") (pinfunction "3_3") (pintype "passive"))
      (node (ref "U1") (pin "68") (pinfunction "REF_H_68") (pintype "input"))
    )
    (net (code "109") (name "REF_L") (class "Default")
      (node (ref "JP9") (pin "1") (pinfunction "1_1") (pintype "passive"))
      (node (ref "U1") (pin "67") (pinfunction "REF_L_67") (pintype "input"))
    )
    (net (code "110") (name "REF_R") (class "Default")
      (node (ref "JP9") (pin "5") (pinfunction "5_5") (pintype "passive"))
      (node (ref "U1") (pin "69") (pinfunction "REF_R_69") (pintype "input"))
    )
    (net (code "111") (name "RESET") (class "Default")
      (node (ref "R3") (pin "1") (pinfunction "1_1") (pintype "passive"))
      (node (ref "U1") (pin "50") (pinfunction "NRST_50") (pintype "input"))
      (node (ref "X1") (pin "3") (pinfunction "KL_3") (pintype "passive"))
    )
    (net (code "112") (name "RES_FET") (class "Default")
      (node (ref "D11") (pin "A") (pinfunction "A_A") (pintype "passive"))
      (node (ref "D15") (pin "C") (pinfunction "C_C") (pintype "passive"))
      (node (ref "U17") (pin "5") (pinfunction "D_5") (pintype "passive"))
      (node (ref "X2") (pin "4") (pinfunction "1_4") (pintype "passive"))
    )
    (net (code "113") (name "SCK") (class "Default")
      (node (ref "U1") (pin "7") (pinfunction "SPI_SCK_7") (pintype "input"))
      (node (ref "X1") (pin "8") (pinfunction "KL_8") (pintype "passive"))
    )
    (net (code "114") (name "SENSE_A") (class "Default")
      (node (ref "C30") (pin "2") (pinfunction "2_2") (pintype "passive"))
      (node (ref "R23") (pin "1") (pinfunction "1_1") (pintype "passive"))
      (node (ref "U1") (pin "16") (pinfunction "ADC_I0_POS_16") (pintype "input"))
    )
    (net (code "115") (name "SENSE_C") (class "Default")
      (node (ref "C31") (pin "2") (pinfunction "2_2") (pintype "passive"))
      (node (ref "R24") (pin "1") (pinfunction "1_1") (pintype "passive"))
      (node (ref "U1") (pin "18") (pinfunction "ADC_I1_POS_18") (pintype "input"))
    )
    (net (code "116") (name "STEP") (class "Default")
      (node (ref "JP10") (pin "2") (pinfunction "2_2") (pintype "passive"))
      (node (ref "U1") (pin "57") (pinfunction "STP_57") (pintype "input"))
    )
    (net (code "117") (name "UART_RX") (class "Default")
      (node (ref "JP6") (pin "1") (pinfunction "1_1") (pintype "passive"))
      (node (ref "U1") (pin "10") (pinfunction "UART_RXD_10") (pintype "input"))
    )
    (net (code "118") (name "UART_TX") (class "Default")
      (node (ref "JP6") (pin "2") (pinfunction "2_2") (pintype "passive"))
      (node (ref "U1") (pin "11") (pinfunction "UART_TXD_11") (pintype "output"))
    )
    (net (code "119") (name "V+") (class "Default")
      (node (ref "C11") (pin "+") (pinfunction "+_+") (pintype "passive"))
      (node (ref "C12") (pin "+") (pinfunction "+_+") (pintype "passive"))
      (node (ref "C13") (pin "1") (pinfunction "1_1") (pintype "passive"))
      (node (ref "C14") (pin "1") (pinfunction "1_1") (pintype "passive"))
      (node (ref "C15") (pin "1") (pinfunction "1_1") (pintype "passive"))
      (node (ref "C16") (pin "1") (pinfunction "1_1") (pintype "passive"))
      (node (ref "C43") (pin "2") (pinfunction "2_2") (pintype "passive"))
      (node (ref "D11") (pin "C") (pinfunction "C_C") (pintype "passive"))
      (node (ref "R13") (pin "2") (pinfunction "2_2") (pintype "passive"))
      (node (ref "R15") (pin "2") (pinfunction "2_2") (pintype "passive"))
      (node (ref "R47") (pin "2") (pinfunction "2_2") (pintype "passive"))
      (node (ref "U10") (pin "5") (pinfunction "D_5") (pintype "passive"))
      (node (ref "U12") (pin "5") (pinfunction "D_5") (pintype "passive"))
      (node (ref "U15") (pin "5") (pinfunction "D_5") (pintype "passive"))
      (node (ref "U20") (pin "4") (pinfunction "CATHODE_4") (pintype "bidirectional"))
      (node (ref "U22") (pin "5") (pinfunction "D_5") (pintype "passive"))
      (node (ref "U23") (pin "7") (pinfunction "VIN_7") (pintype "power_in"))
      (node (ref "U6") (pin "5") (pinfunction "D_5") (pintype "passive"))
      (node (ref "X2") (pin "2") (pinfunction "1_2") (pintype "passive"))
    )
    (net (code "120") (name "V_EXT") (class "Default")
      (node (ref "R18") (pin "1") (pinfunction "1_1") (pintype "passive"))
      (node (ref "R19") (pin "2") (pinfunction "2_2") (pintype "passive"))
      (node (ref "X1") (pin "13") (pinfunction "KL_13") (pintype "passive"))
    )
    (net (code "121") (name "V_GD") (class "Default")
      (node (ref "C10") (pin "2") (pinfunction "2_2") (pintype "passive"))
      (node (ref "C45") (pin "1") (pinfunction "1_1") (pintype "passive"))
      (node (ref "C7") (pin "2") (pinfunction "2_2") (pintype "passive"))
      (node (ref "C8") (pin "2") (pinfunction "2_2") (pintype "passive"))
      (node (ref "C9") (pin "2") (pinfunction "2_2") (pintype "passive"))
      (node (ref "D14") (pin "C") (pinfunction "C_C") (pintype "passive"))
      (node (ref "D2") (pin "A") (pinfunction "A_A") (pintype "passive"))
      (node (ref "D3") (pin "A") (pinfunction "A_A") (pintype "passive"))
      (node (ref "D4") (pin "A") (pinfunction "A_A") (pintype "passive"))
      (node (ref "D5") (pin "A") (pinfunction "A_A") (pintype "passive"))
      (node (ref "JP4") (pin "1") (pinfunction "1_1") (pintype "passive"))
      (node (ref "R49") (pin "2") (pinfunction "2_2") (pintype "passive"))
      (node (ref "U14") (pin "2") (pinfunction "VDD_2") (pintype "bidirectional"))
      (node (ref "U2") (pin "1") (pinfunction "VDD_1") (pintype "power_in"))
      (node (ref "U3") (pin "1") (pinfunction "VDD_1") (pintype "power_in"))
      (node (ref "U4") (pin "1") (pinfunction "VDD_1") (pintype "power_in"))
      (node (ref "U5") (pin "1") (pinfunction "VDD_1") (pintype "power_in"))
    )
    (net (code "122") (name "V_INT") (class "Default")
      (node (ref "R15") (pin "1") (pinfunction "1_1") (pintype "passive"))
      (node (ref "R16") (pin "2") (pinfunction "2_2") (pintype "passive"))
      (node (ref "X1") (pin "14") (pinfunction "KL_14") (pintype "passive"))
    )
    (net (code "123") (name "V_INT_TMC") (class "Default")
      (node (ref "C25") (pin "1") (pinfunction "1_1") (pintype "passive"))
      (node (ref "R13") (pin "1") (pinfunction "1_1") (pintype "passive"))
      (node (ref "R14") (pin "2") (pinfunction "2_2") (pintype "passive"))
      (node (ref "U1") (pin "20") (pinfunction "ADC_VM_20") (pintype "input"))
    )
    (net (code "124") (name "V_MOT_IN") (class "Default")
      (node (ref "C39") (pin "2") (pinfunction "2_2") (pintype "passive"))
      (node (ref "R18") (pin "2") (pinfunction "2_2") (pintype "passive"))
      (node (ref "U20") (pin "3") (pinfunction "EN_3") (pintype "bidirectional"))
      (node (ref "U20") (pin "6") (pinfunction "ANODE_6") (pintype "bidirectional"))
      (node (ref "U22") (pin "1") (pinfunction "S_1") (pintype "passive"))
      (node (ref "U22") (pin "2") (pinfunction "S_2") (pintype "passive"))
      (node (ref "U22") (pin "3") (pinfunction "S_3") (pintype "passive"))
      (node (ref "X2") (pin "3") (pinfunction "1_3") (pintype "passive"))
    )
    (net (code "125") (name "V_SENSE{slash}2") (class "Default")
      (node (ref "C1") (pin "2") (pinfunction "2_2") (pintype "passive"))
      (node (ref "C2") (pin "2") (pinfunction "2_2") (pintype "passive"))
      (node (ref "R1") (pin "1") (pinfunction "1_1") (pintype "passive"))
      (node (ref "R2") (pin "2") (pinfunction "2_2") (pintype "passive"))
      (node (ref "U1") (pin "17") (pinfunction "ADC_I0_NEG_17") (pintype "input"))
      (node (ref "U1") (pin "19") (pinfunction "ADC_I1_NEG_19") (pintype "input"))
      (node (ref "U8") (pin "3") (pinfunction "REF2_3") (pintype "bidirectional"))
      (node (ref "U8") (pin "7") (pinfunction "REF1_7") (pintype "bidirectional"))
      (node (ref "U9") (pin "3") (pinfunction "REF2_3") (pintype "bidirectional"))
      (node (ref "U9") (pin "7") (pinfunction "REF1_7") (pintype "bidirectional"))
    )
    (net (code "126") (name "unconnected-(X1G-KL-Pad15)") (class "Default")
      (node (ref "X1") (pin "15") (pinfunction "KL_15") (pintype "passive"))
    )
    (net (code "127") (name "unconnected-(Y1-TRI_STATE-Pad1)") (class "Default")
      (node (ref "Y1") (pin "1") (pinfunction "TRI_STATE_1") (pintype "input"))
    )
  )
)
